# Sheet1.net
KiCad netlist of a schematic drawn in Altium Designer
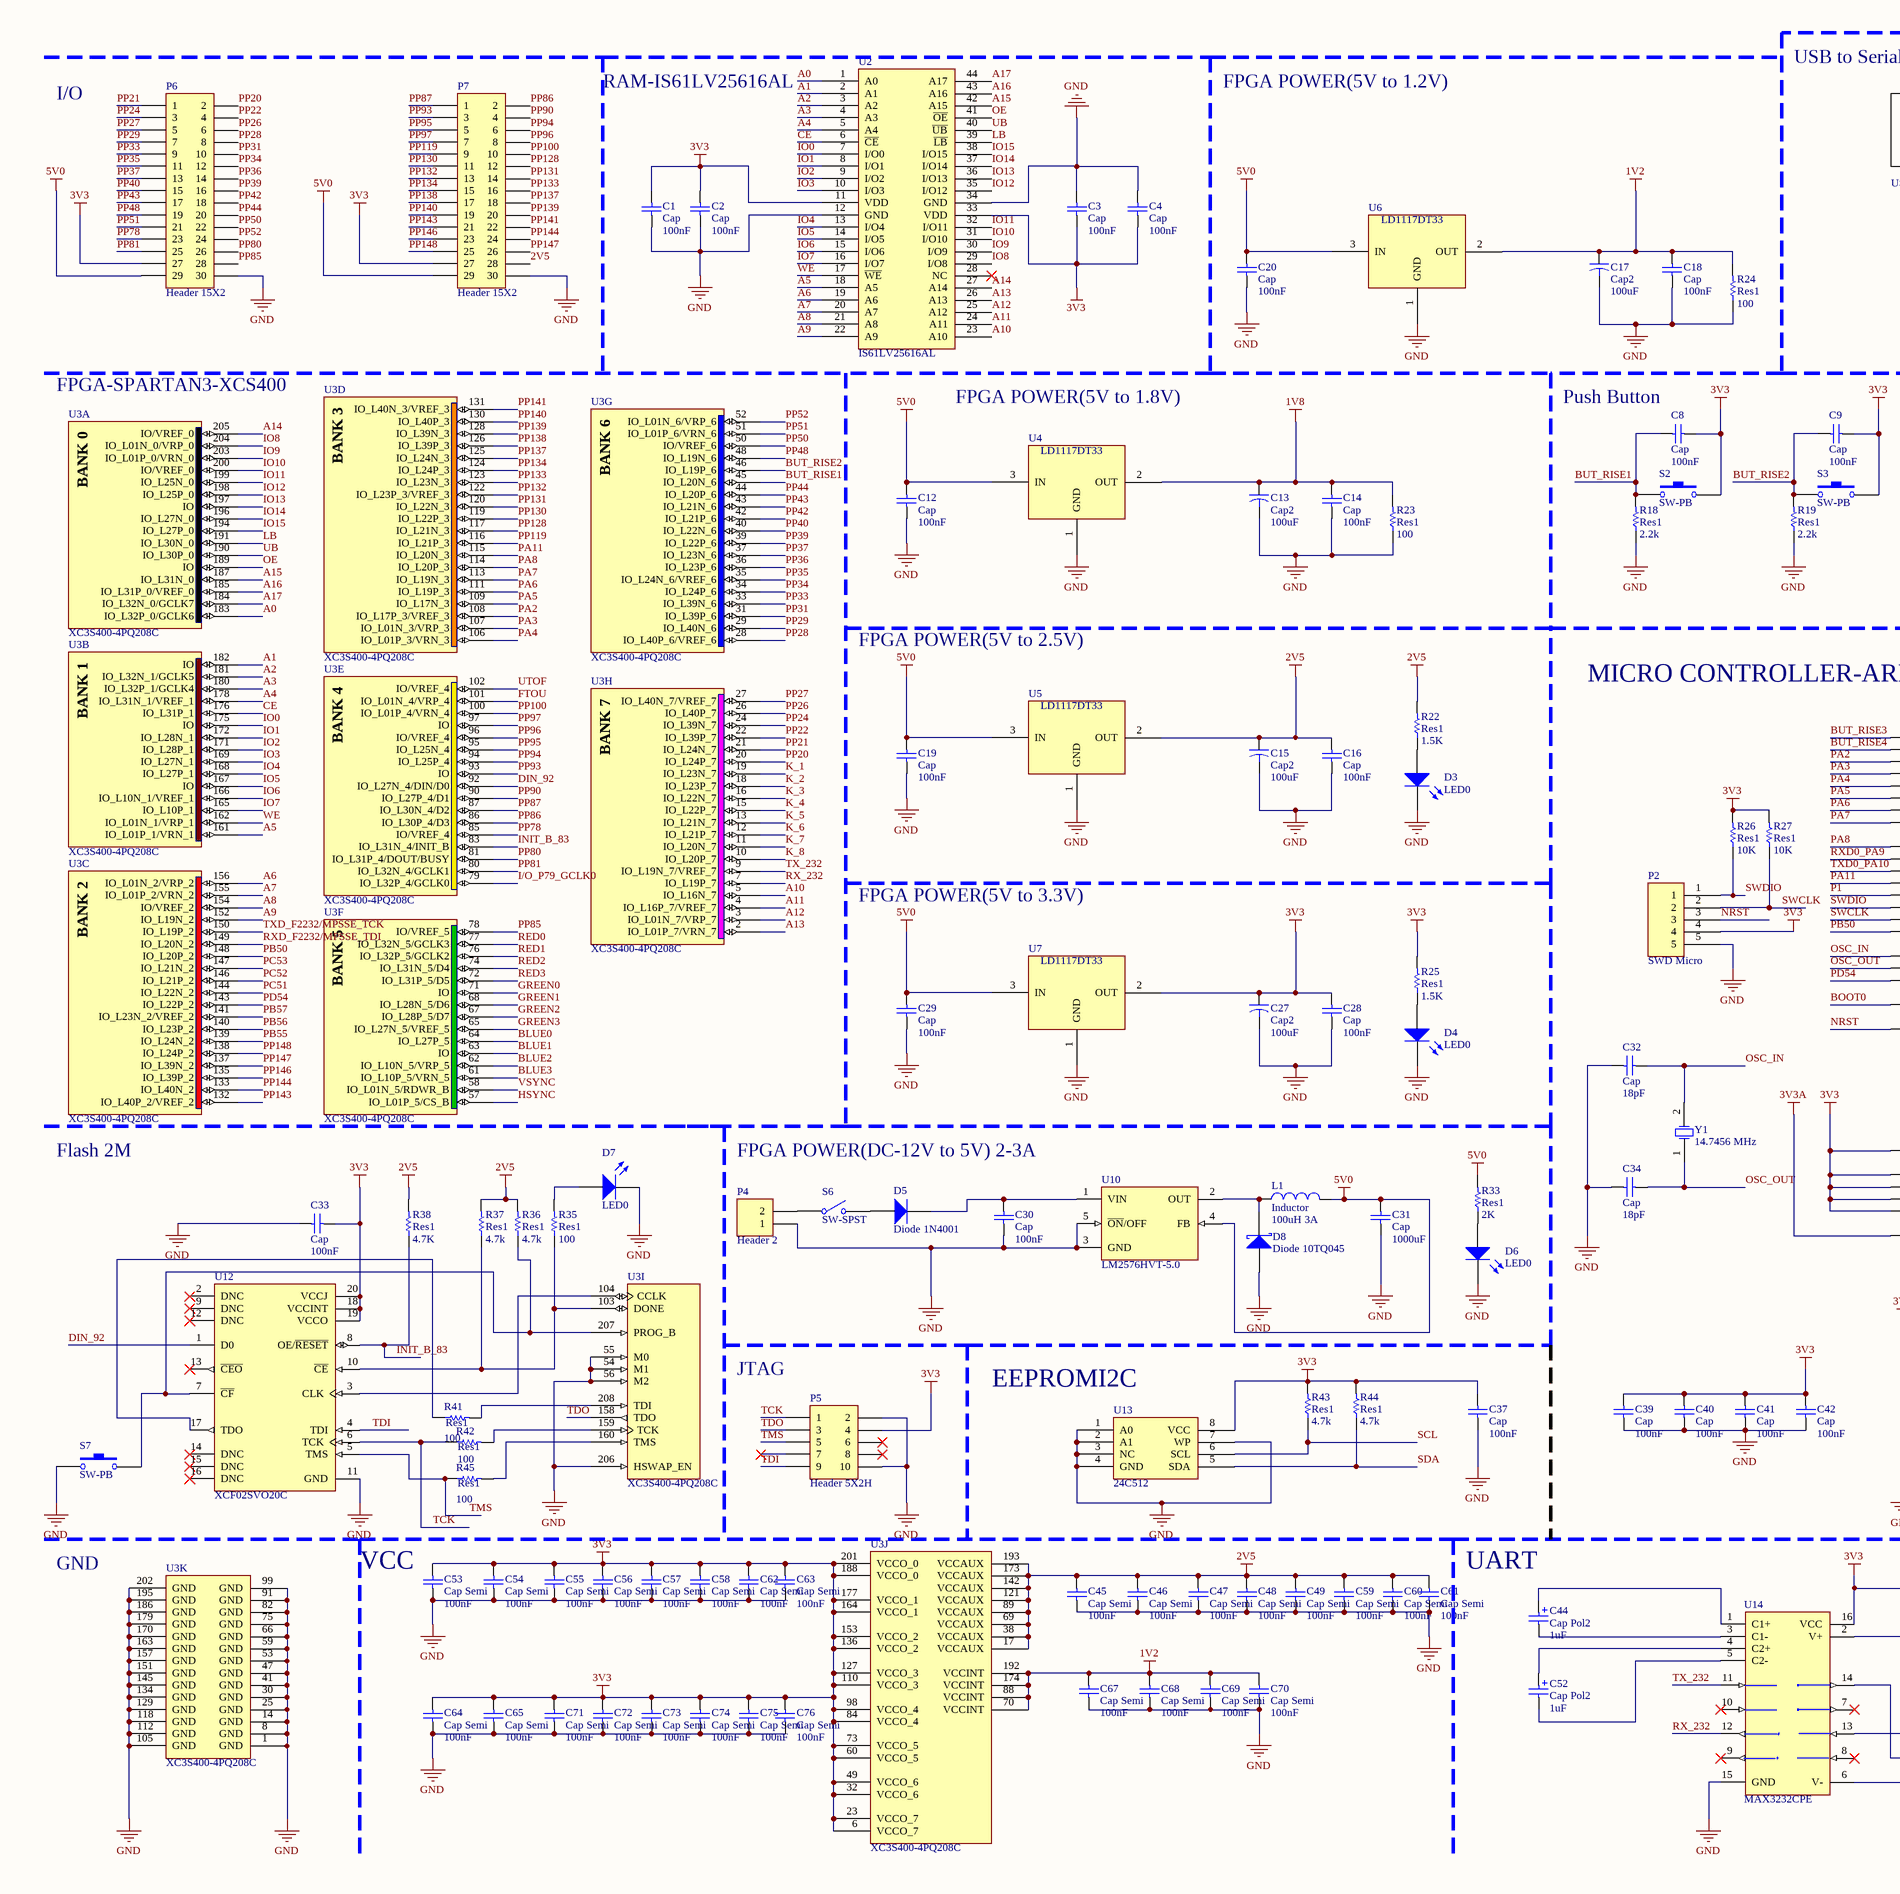
[diagram p0: Sheet1.SchDoc, left]
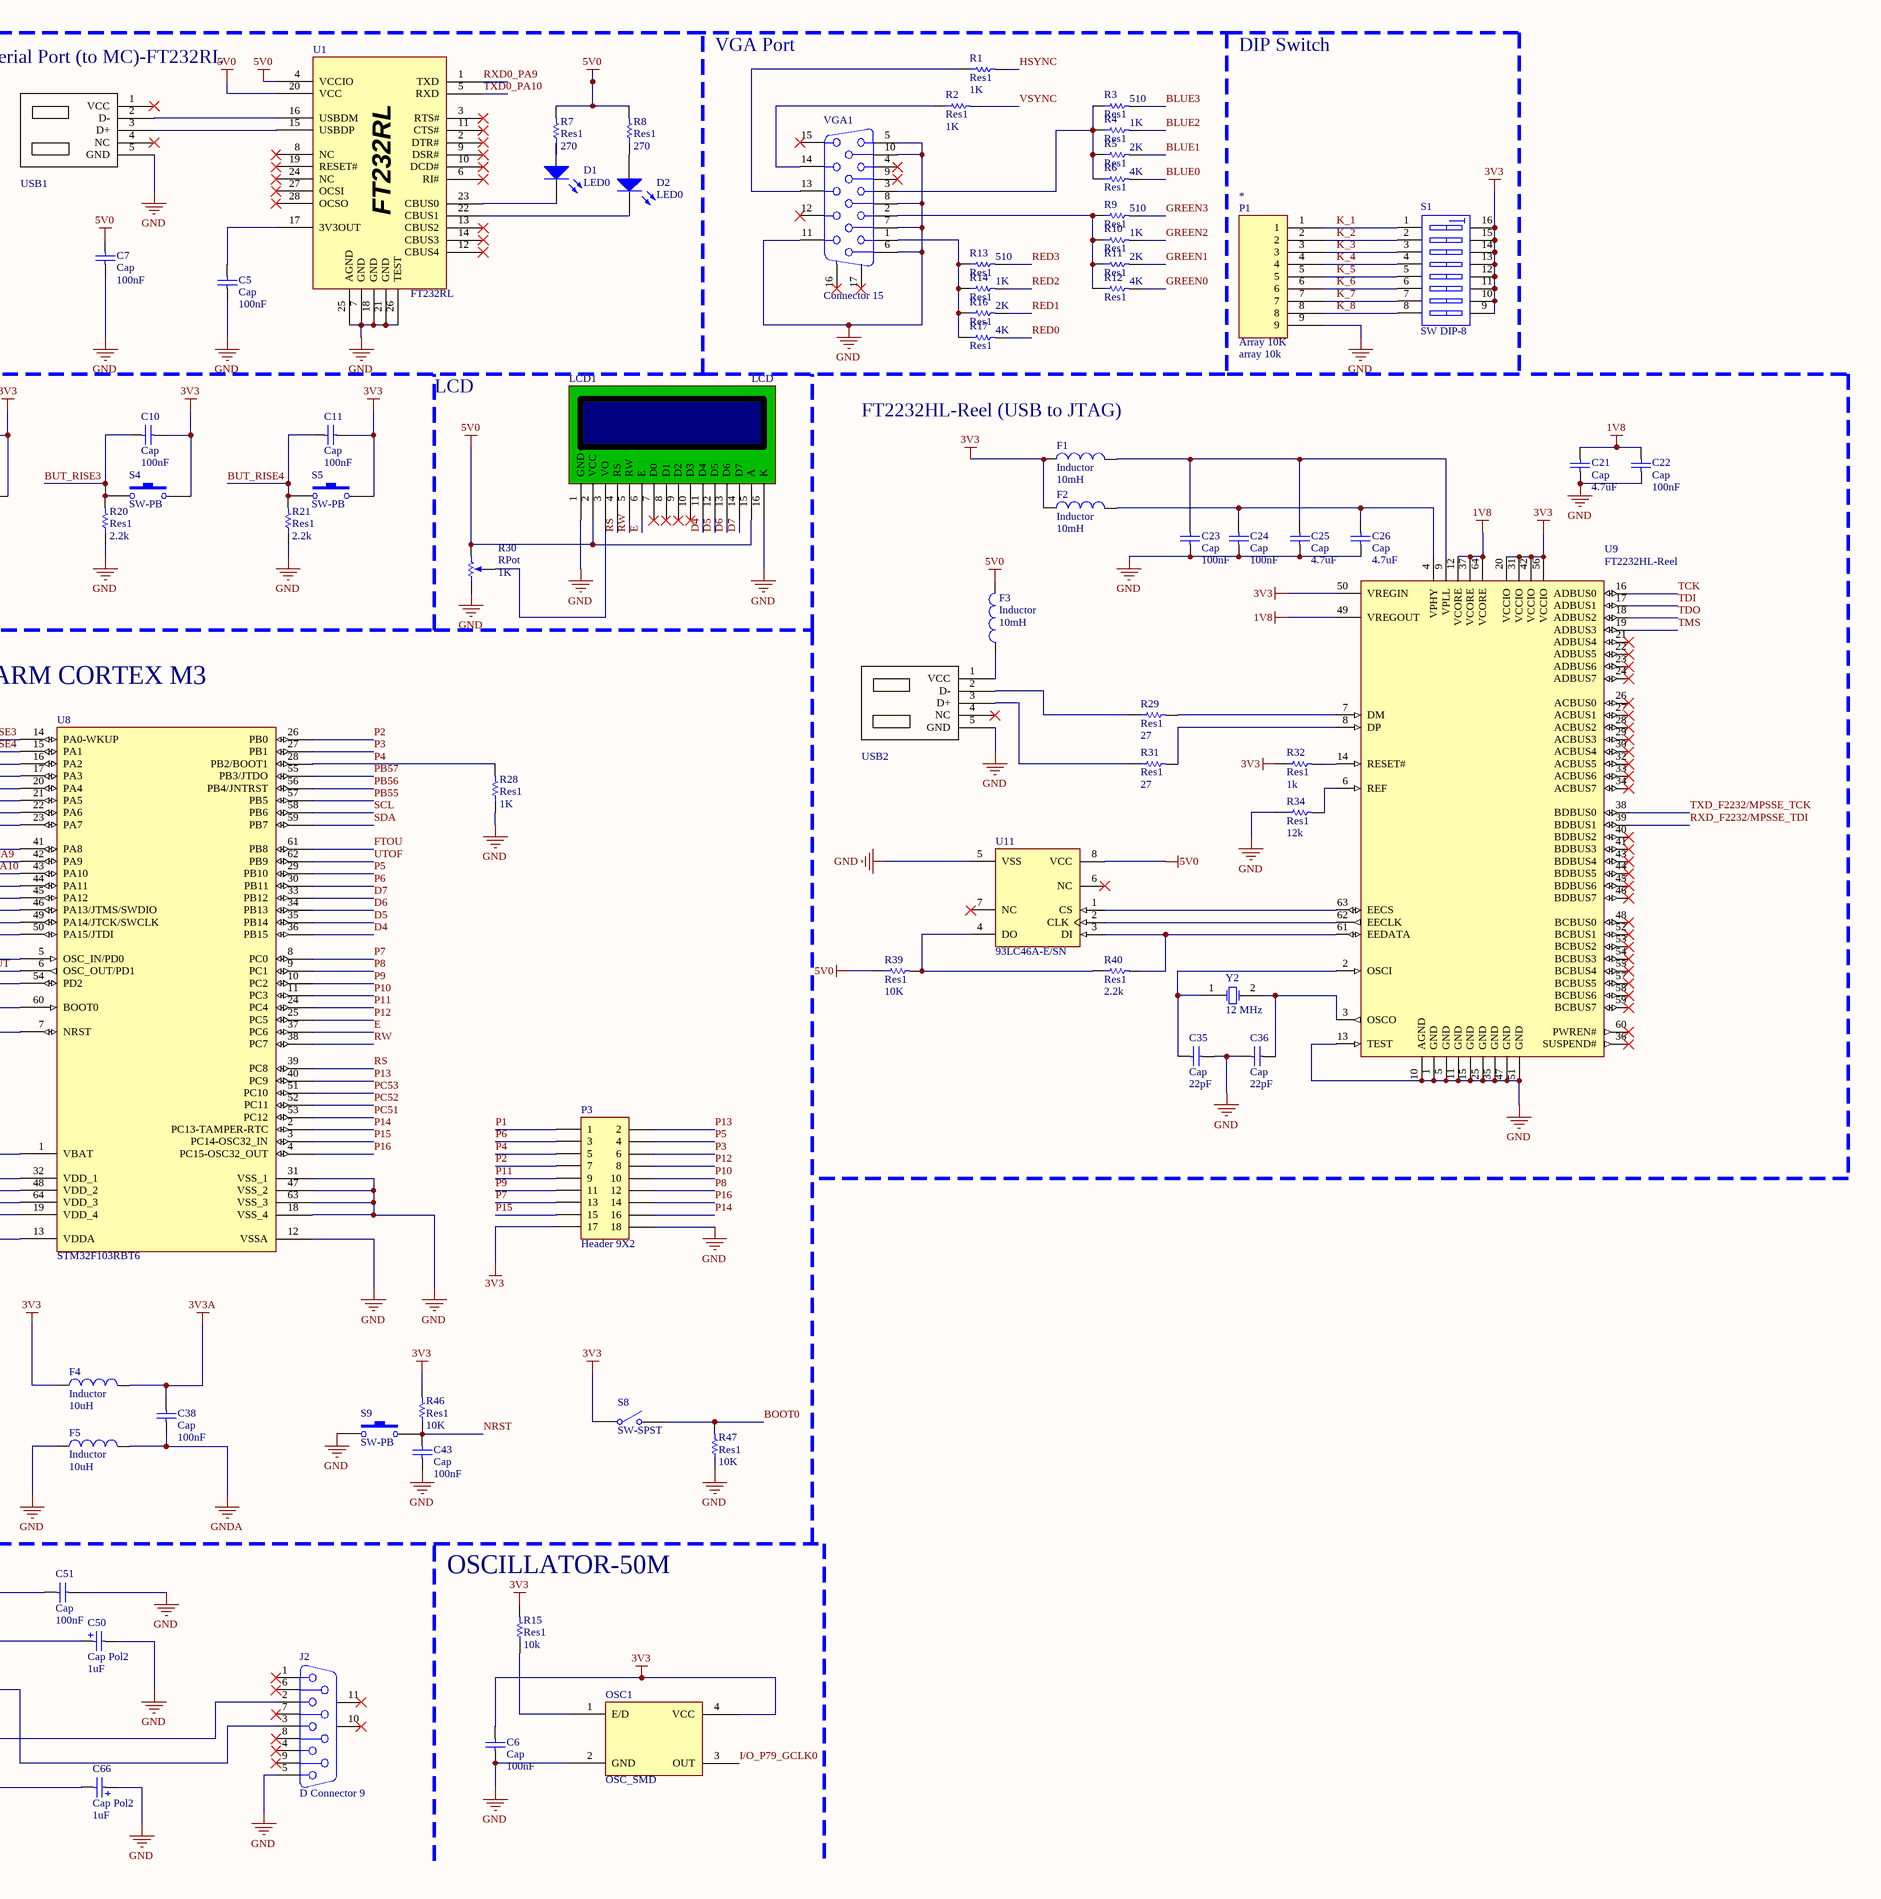
[diagram p1: Sheet1.SchDoc, right]

(export (version "E")
  (design (tool "Eeschema 10.0.6"))
  (components
    (comp (ref "*") (value "array 10k") (footprint "Aray 9") (libsource (lib "Array10k") (part "array 10k")))
    (comp (ref "C1")
      (value "Cap")
      (footprint "SMD_805")
      (description "Capacitor")
      (fields (field (name "ALTIUM_VALUE") "100nF") (field (name "PUBLISHER") "Altium Limited"))
      (libsource (lib "Miscellaneous Devices") (part "Cap"))
    )
    (comp (ref "C2")
      (value "Cap")
      (footprint "SMD_805")
      (description "Capacitor")
      (fields (field (name "ALTIUM_VALUE") "100nF") (field (name "PUBLISHER") "Altium Limited"))
      (libsource (lib "Miscellaneous Devices") (part "Cap"))
    )
    (comp (ref "C3")
      (value "Cap")
      (footprint "SMD_805")
      (description "Capacitor")
      (fields (field (name "ALTIUM_VALUE") "100nF") (field (name "PUBLISHER") "Altium Limited"))
      (libsource (lib "Miscellaneous Devices") (part "Cap"))
    )
    (comp (ref "C4")
      (value "Cap")
      (footprint "SMD_805")
      (description "Capacitor")
      (fields (field (name "ALTIUM_VALUE") "100nF") (field (name "PUBLISHER") "Altium Limited"))
      (libsource (lib "Miscellaneous Devices") (part "Cap"))
    )
    (comp (ref "C5")
      (value "Cap")
      (footprint "SMD_805")
      (description "Capacitor")
      (fields (field (name "ALTIUM_VALUE") "100nF") (field (name "PUBLISHER") "Altium Limited"))
      (libsource (lib "Miscellaneous Devices") (part "Cap"))
    )
    (comp (ref "C6")
      (value "Cap")
      (footprint "SMD_805")
      (description "Capacitor")
      (fields (field (name "ALTIUM_VALUE") "100nF") (field (name "PUBLISHER") "Altium Limited"))
      (libsource (lib "Miscellaneous Devices") (part "Cap"))
    )
    (comp (ref "C7")
      (value "Cap")
      (footprint "SMD_805")
      (description "Capacitor")
      (fields (field (name "ALTIUM_VALUE") "100nF") (field (name "PUBLISHER") "Altium Limited"))
      (libsource (lib "Miscellaneous Devices") (part "Cap"))
    )
    (comp (ref "C8")
      (value "Cap")
      (footprint "SMD_805")
      (description "Capacitor")
      (fields (field (name "ALTIUM_VALUE") "100nF") (field (name "PUBLISHER") "Altium Limited"))
      (libsource (lib "Miscellaneous Devices") (part "Cap"))
    )
    (comp (ref "C9")
      (value "Cap")
      (footprint "SMD_805")
      (description "Capacitor")
      (fields (field (name "ALTIUM_VALUE") "100nF") (field (name "PUBLISHER") "Altium Limited"))
      (libsource (lib "Miscellaneous Devices") (part "Cap"))
    )
    (comp (ref "C10")
      (value "Cap")
      (footprint "SMD_805")
      (description "Capacitor")
      (fields (field (name "ALTIUM_VALUE") "100nF") (field (name "PUBLISHER") "Altium Limited"))
      (libsource (lib "Miscellaneous Devices") (part "Cap"))
    )
    (comp (ref "C11")
      (value "Cap")
      (footprint "SMD_805")
      (description "Capacitor")
      (fields (field (name "ALTIUM_VALUE") "100nF") (field (name "PUBLISHER") "Altium Limited"))
      (libsource (lib "Miscellaneous Devices") (part "Cap"))
    )
    (comp (ref "C12")
      (value "Cap")
      (footprint "SMD_805")
      (description "Capacitor")
      (fields (field (name "ALTIUM_VALUE") "100nF") (field (name "PUBLISHER") "Altium Limited"))
      (libsource (lib "Miscellaneous Devices") (part "Cap"))
    )
    (comp (ref "C13")
      (value "Cap2")
      (footprint "C_B")
      (description "Capacitor")
      (fields (field (name "ALTIUM_VALUE") "100uF") (field (name "PUBLISHER") "Altium Limited"))
      (libsource (lib "Miscellaneous Devices") (part "Cap2"))
    )
    (comp (ref "C14")
      (value "Cap")
      (footprint "SMD_805")
      (description "Capacitor")
      (fields (field (name "ALTIUM_VALUE") "100nF") (field (name "PUBLISHER") "Altium Limited"))
      (libsource (lib "Miscellaneous Devices") (part "Cap"))
    )
    (comp (ref "C15")
      (value "Cap2")
      (footprint "C_B")
      (description "Capacitor")
      (fields (field (name "ALTIUM_VALUE") "100uF") (field (name "PUBLISHER") "Altium Limited"))
      (libsource (lib "Miscellaneous Devices") (part "Cap2"))
    )
    (comp (ref "C16")
      (value "Cap")
      (footprint "SMD_805")
      (description "Capacitor")
      (fields (field (name "ALTIUM_VALUE") "100nF") (field (name "PUBLISHER") "Altium Limited"))
      (libsource (lib "Miscellaneous Devices") (part "Cap"))
    )
    (comp (ref "C17")
      (value "Cap2")
      (footprint "C_B")
      (description "Capacitor")
      (fields (field (name "ALTIUM_VALUE") "100uF") (field (name "PUBLISHER") "Altium Limited"))
      (libsource (lib "Miscellaneous Devices") (part "Cap2"))
    )
    (comp (ref "C18")
      (value "Cap")
      (footprint "SMD_805")
      (description "Capacitor")
      (fields (field (name "ALTIUM_VALUE") "100nF") (field (name "PUBLISHER") "Altium Limited"))
      (libsource (lib "Miscellaneous Devices") (part "Cap"))
    )
    (comp (ref "C19")
      (value "Cap")
      (footprint "SMD_805")
      (description "Capacitor")
      (fields (field (name "ALTIUM_VALUE") "100nF") (field (name "PUBLISHER") "Altium Limited"))
      (libsource (lib "Miscellaneous Devices") (part "Cap"))
    )
    (comp (ref "C20")
      (value "Cap")
      (footprint "SMD_805")
      (description "Capacitor")
      (fields (field (name "ALTIUM_VALUE") "100nF") (field (name "PUBLISHER") "Altium Limited"))
      (libsource (lib "Miscellaneous Devices") (part "Cap"))
    )
    (comp (ref "C21")
      (value "Cap")
      (footprint "SMD_805")
      (description "Capacitor")
      (fields (field (name "ALTIUM_VALUE") "4.7uF") (field (name "PUBLISHER") "Altium Limited"))
      (libsource (lib "Miscellaneous Devices") (part "Cap"))
    )
    (comp (ref "C22")
      (value "Cap")
      (footprint "SMD_805")
      (description "Capacitor")
      (fields (field (name "ALTIUM_VALUE") "100nF") (field (name "PUBLISHER") "Altium Limited"))
      (libsource (lib "Miscellaneous Devices") (part "Cap"))
    )
    (comp (ref "C23")
      (value "Cap")
      (footprint "SMD_805")
      (description "Capacitor")
      (fields (field (name "ALTIUM_VALUE") "100nF") (field (name "PUBLISHER") "Altium Limited"))
      (libsource (lib "Miscellaneous Devices") (part "Cap"))
    )
    (comp (ref "C24")
      (value "Cap")
      (footprint "SMD_805")
      (description "Capacitor")
      (fields (field (name "ALTIUM_VALUE") "100nF") (field (name "PUBLISHER") "Altium Limited"))
      (libsource (lib "Miscellaneous Devices") (part "Cap"))
    )
    (comp (ref "C25")
      (value "Cap")
      (footprint "SMD_805")
      (description "Capacitor")
      (fields (field (name "ALTIUM_VALUE") "4.7uF") (field (name "PUBLISHER") "Altium Limited"))
      (libsource (lib "Miscellaneous Devices") (part "Cap"))
    )
    (comp (ref "C26")
      (value "Cap")
      (footprint "SMD_805")
      (description "Capacitor")
      (fields (field (name "ALTIUM_VALUE") "4.7uF") (field (name "PUBLISHER") "Altium Limited"))
      (libsource (lib "Miscellaneous Devices") (part "Cap"))
    )
    (comp (ref "C27")
      (value "Cap2")
      (footprint "C_B")
      (description "Capacitor")
      (fields (field (name "ALTIUM_VALUE") "100uF") (field (name "PUBLISHER") "Altium Limited"))
      (libsource (lib "Miscellaneous Devices") (part "Cap2"))
    )
    (comp (ref "C28")
      (value "Cap")
      (footprint "SMD_805")
      (description "Capacitor")
      (fields (field (name "ALTIUM_VALUE") "100nF") (field (name "PUBLISHER") "Altium Limited"))
      (libsource (lib "Miscellaneous Devices") (part "Cap"))
    )
    (comp (ref "C29")
      (value "Cap")
      (footprint "SMD_805")
      (description "Capacitor")
      (fields (field (name "ALTIUM_VALUE") "100nF") (field (name "PUBLISHER") "Altium Limited"))
      (libsource (lib "Miscellaneous Devices") (part "Cap"))
    )
    (comp (ref "C30")
      (value "Cap")
      (footprint "C_CYL_SMD2")
      (description "Capacitor")
      (fields (field (name "ALTIUM_VALUE") "100nF") (field (name "PUBLISHER") "Altium Limited"))
      (libsource (lib "Miscellaneous Devices") (part "Cap"))
    )
    (comp (ref "C31")
      (value "Cap")
      (footprint "C_CYL_SMD")
      (description "Capacitor")
      (fields (field (name "ALTIUM_VALUE") "1000uF") (field (name "PUBLISHER") "Altium Limited"))
      (libsource (lib "Miscellaneous Devices") (part "Cap"))
    )
    (comp (ref "C32")
      (value "Cap")
      (footprint "SMD_805")
      (description "Capacitor")
      (fields (field (name "ALTIUM_VALUE") "18pF") (field (name "PUBLISHER") "Altium Limited"))
      (libsource (lib "Miscellaneous Devices") (part "Cap"))
    )
    (comp (ref "C33")
      (value "Cap")
      (footprint "SMD_805")
      (description "Capacitor")
      (fields (field (name "ALTIUM_VALUE") "100nF") (field (name "PUBLISHER") "Altium Limited"))
      (libsource (lib "Miscellaneous Devices") (part "Cap"))
    )
    (comp (ref "C34")
      (value "Cap")
      (footprint "SMD_805")
      (description "Capacitor")
      (fields (field (name "ALTIUM_VALUE") "18pF") (field (name "PUBLISHER") "Altium Limited"))
      (libsource (lib "Miscellaneous Devices") (part "Cap"))
    )
    (comp (ref "C35")
      (value "Cap")
      (footprint "SMD_805")
      (description "Capacitor")
      (fields (field (name "ALTIUM_VALUE") "22pF") (field (name "PUBLISHER") "Altium Limited"))
      (libsource (lib "Miscellaneous Devices") (part "Cap"))
    )
    (comp (ref "C36")
      (value "Cap")
      (footprint "SMD_805")
      (description "Capacitor")
      (fields (field (name "ALTIUM_VALUE") "22pF") (field (name "PUBLISHER") "Altium Limited"))
      (libsource (lib "Miscellaneous Devices") (part "Cap"))
    )
    (comp (ref "C37")
      (value "Cap")
      (footprint "SMD_805")
      (description "Capacitor")
      (fields (field (name "ALTIUM_VALUE") "100nF") (field (name "PUBLISHER") "Altium Limited"))
      (libsource (lib "Miscellaneous Devices") (part "Cap"))
    )
    (comp (ref "C38")
      (value "Cap")
      (footprint "SMD_805")
      (description "Capacitor")
      (fields (field (name "ALTIUM_VALUE") "100nF") (field (name "PUBLISHER") "Altium Limited"))
      (libsource (lib "Miscellaneous Devices") (part "Cap"))
    )
    (comp (ref "C39")
      (value "Cap")
      (footprint "SMD_805")
      (description "Capacitor")
      (fields (field (name "ALTIUM_VALUE") "100nF") (field (name "PUBLISHER") "Altium Limited"))
      (libsource (lib "Miscellaneous Devices") (part "Cap"))
    )
    (comp (ref "C40")
      (value "Cap")
      (footprint "SMD_805")
      (description "Capacitor")
      (fields (field (name "ALTIUM_VALUE") "100nF") (field (name "PUBLISHER") "Altium Limited"))
      (libsource (lib "Miscellaneous Devices") (part "Cap"))
    )
    (comp (ref "C41")
      (value "Cap")
      (footprint "SMD_805")
      (description "Capacitor")
      (fields (field (name "ALTIUM_VALUE") "100nF") (field (name "PUBLISHER") "Altium Limited"))
      (libsource (lib "Miscellaneous Devices") (part "Cap"))
    )
    (comp (ref "C42")
      (value "Cap")
      (footprint "SMD_805")
      (description "Capacitor")
      (fields (field (name "ALTIUM_VALUE") "100nF") (field (name "PUBLISHER") "Altium Limited"))
      (libsource (lib "Miscellaneous Devices") (part "Cap"))
    )
    (comp (ref "C43")
      (value "Cap")
      (footprint "SMD_805")
      (description "Capacitor")
      (fields (field (name "ALTIUM_VALUE") "100nF") (field (name "PUBLISHER") "Altium Limited"))
      (libsource (lib "Miscellaneous Devices") (part "Cap"))
    )
    (comp (ref "C44")
      (value "Cap Pol2")
      (footprint "C_B")
      (description "Polarized Capacitor (Axial)")
      (fields (field (name "ALTIUM_VALUE") "1uF") (field (name "PUBLISHER") "Altium Limited"))
      (libsource (lib "Miscellaneous Devices") (part "Cap Pol2"))
    )
    (comp (ref "C45")
      (value "Cap Semi")
      (footprint "SMD_805")
      (description "Capacitor (Semiconductor SIM Model)")
      (fields (field (name "ALTIUM_VALUE") "100nF") (field (name "PUBLISHER") "Altium Limited"))
      (libsource (lib "Miscellaneous Devices") (part "Cap Semi"))
    )
    (comp (ref "C46")
      (value "Cap Semi")
      (footprint "SMD_805")
      (description "Capacitor (Semiconductor SIM Model)")
      (fields (field (name "ALTIUM_VALUE") "100nF") (field (name "PUBLISHER") "Altium Limited"))
      (libsource (lib "Miscellaneous Devices") (part "Cap Semi"))
    )
    (comp (ref "C47")
      (value "Cap Semi")
      (footprint "SMD_805")
      (description "Capacitor (Semiconductor SIM Model)")
      (fields (field (name "ALTIUM_VALUE") "100nF") (field (name "PUBLISHER") "Altium Limited"))
      (libsource (lib "Miscellaneous Devices") (part "Cap Semi"))
    )
    (comp (ref "C48")
      (value "Cap Semi")
      (footprint "SMD_805")
      (description "Capacitor (Semiconductor SIM Model)")
      (fields (field (name "ALTIUM_VALUE") "100nF") (field (name "PUBLISHER") "Altium Limited"))
      (libsource (lib "Miscellaneous Devices") (part "Cap Semi"))
    )
    (comp (ref "C49")
      (value "Cap Semi")
      (footprint "SMD_805")
      (description "Capacitor (Semiconductor SIM Model)")
      (fields (field (name "ALTIUM_VALUE") "100nF") (field (name "PUBLISHER") "Altium Limited"))
      (libsource (lib "Miscellaneous Devices") (part "Cap Semi"))
    )
    (comp (ref "C50")
      (value "Cap Pol2")
      (footprint "C_B")
      (description "Polarized Capacitor (Axial)")
      (fields (field (name "ALTIUM_VALUE") "1uF") (field (name "PUBLISHER") "Altium Limited"))
      (libsource (lib "Miscellaneous Devices") (part "Cap Pol2"))
    )
    (comp (ref "C51")
      (value "Cap")
      (footprint "SMD_805")
      (description "Capacitor")
      (fields (field (name "ALTIUM_VALUE") "100nF") (field (name "PUBLISHER") "Altium Limited"))
      (libsource (lib "Miscellaneous Devices") (part "Cap"))
    )
    (comp (ref "C52")
      (value "Cap Pol2")
      (footprint "C_B")
      (description "Polarized Capacitor (Axial)")
      (fields (field (name "ALTIUM_VALUE") "1uF") (field (name "PUBLISHER") "Altium Limited"))
      (libsource (lib "Miscellaneous Devices") (part "Cap Pol2"))
    )
    (comp (ref "C53")
      (value "Cap Semi")
      (footprint "SMD_805")
      (description "Capacitor (Semiconductor SIM Model)")
      (fields (field (name "ALTIUM_VALUE") "100nF") (field (name "PUBLISHER") "Altium Limited"))
      (libsource (lib "Miscellaneous Devices") (part "Cap Semi"))
    )
    (comp (ref "C54")
      (value "Cap Semi")
      (footprint "SMD_805")
      (description "Capacitor (Semiconductor SIM Model)")
      (fields (field (name "ALTIUM_VALUE") "100nF") (field (name "PUBLISHER") "Altium Limited"))
      (libsource (lib "Miscellaneous Devices") (part "Cap Semi"))
    )
    (comp (ref "C55")
      (value "Cap Semi")
      (footprint "SMD_805")
      (description "Capacitor (Semiconductor SIM Model)")
      (fields (field (name "ALTIUM_VALUE") "100nF") (field (name "PUBLISHER") "Altium Limited"))
      (libsource (lib "Miscellaneous Devices") (part "Cap Semi"))
    )
    (comp (ref "C56")
      (value "Cap Semi")
      (footprint "SMD_805")
      (description "Capacitor (Semiconductor SIM Model)")
      (fields (field (name "ALTIUM_VALUE") "100nF") (field (name "PUBLISHER") "Altium Limited"))
      (libsource (lib "Miscellaneous Devices") (part "Cap Semi"))
    )
    (comp (ref "C57")
      (value "Cap Semi")
      (footprint "SMD_805")
      (description "Capacitor (Semiconductor SIM Model)")
      (fields (field (name "ALTIUM_VALUE") "100nF") (field (name "PUBLISHER") "Altium Limited"))
      (libsource (lib "Miscellaneous Devices") (part "Cap Semi"))
    )
    (comp (ref "C58")
      (value "Cap Semi")
      (footprint "SMD_805")
      (description "Capacitor (Semiconductor SIM Model)")
      (fields (field (name "ALTIUM_VALUE") "100nF") (field (name "PUBLISHER") "Altium Limited"))
      (libsource (lib "Miscellaneous Devices") (part "Cap Semi"))
    )
    (comp (ref "C59")
      (value "Cap Semi")
      (footprint "SMD_805")
      (description "Capacitor (Semiconductor SIM Model)")
      (fields (field (name "ALTIUM_VALUE") "100nF") (field (name "PUBLISHER") "Altium Limited"))
      (libsource (lib "Miscellaneous Devices") (part "Cap Semi"))
    )
    (comp (ref "C60")
      (value "Cap Semi")
      (footprint "SMD_805")
      (description "Capacitor (Semiconductor SIM Model)")
      (fields (field (name "ALTIUM_VALUE") "100nF") (field (name "PUBLISHER") "Altium Limited"))
      (libsource (lib "Miscellaneous Devices") (part "Cap Semi"))
    )
    (comp (ref "C61")
      (value "Cap Semi")
      (footprint "SMD_805")
      (description "Capacitor (Semiconductor SIM Model)")
      (fields (field (name "ALTIUM_VALUE") "100nF") (field (name "PUBLISHER") "Altium Limited"))
      (libsource (lib "Miscellaneous Devices") (part "Cap Semi"))
    )
    (comp (ref "C62")
      (value "Cap Semi")
      (footprint "SMD_805")
      (description "Capacitor (Semiconductor SIM Model)")
      (fields (field (name "ALTIUM_VALUE") "100nF") (field (name "PUBLISHER") "Altium Limited"))
      (libsource (lib "Miscellaneous Devices") (part "Cap Semi"))
    )
    (comp (ref "C63")
      (value "Cap Semi")
      (footprint "SMD_805")
      (description "Capacitor (Semiconductor SIM Model)")
      (fields (field (name "ALTIUM_VALUE") "100nF") (field (name "PUBLISHER") "Altium Limited"))
      (libsource (lib "Miscellaneous Devices") (part "Cap Semi"))
    )
    (comp (ref "C64")
      (value "Cap Semi")
      (footprint "SMD_805")
      (description "Capacitor (Semiconductor SIM Model)")
      (fields (field (name "ALTIUM_VALUE") "100nF") (field (name "PUBLISHER") "Altium Limited"))
      (libsource (lib "Miscellaneous Devices") (part "Cap Semi"))
    )
    (comp (ref "C65")
      (value "Cap Semi")
      (footprint "SMD_805")
      (description "Capacitor (Semiconductor SIM Model)")
      (fields (field (name "ALTIUM_VALUE") "100nF") (field (name "PUBLISHER") "Altium Limited"))
      (libsource (lib "Miscellaneous Devices") (part "Cap Semi"))
    )
    (comp (ref "C66")
      (value "Cap Pol2")
      (footprint "C_B")
      (description "Polarized Capacitor (Axial)")
      (fields (field (name "ALTIUM_VALUE") "1uF") (field (name "PUBLISHER") "Altium Limited"))
      (libsource (lib "Miscellaneous Devices") (part "Cap Pol2"))
    )
    (comp (ref "C67")
      (value "Cap Semi")
      (footprint "SMD_805")
      (description "Capacitor (Semiconductor SIM Model)")
      (fields (field (name "ALTIUM_VALUE") "100nF") (field (name "PUBLISHER") "Altium Limited"))
      (libsource (lib "Miscellaneous Devices") (part "Cap Semi"))
    )
    (comp (ref "C68")
      (value "Cap Semi")
      (footprint "SMD_805")
      (description "Capacitor (Semiconductor SIM Model)")
      (fields (field (name "ALTIUM_VALUE") "100nF") (field (name "PUBLISHER") "Altium Limited"))
      (libsource (lib "Miscellaneous Devices") (part "Cap Semi"))
    )
    (comp (ref "C69")
      (value "Cap Semi")
      (footprint "SMD_805")
      (description "Capacitor (Semiconductor SIM Model)")
      (fields (field (name "ALTIUM_VALUE") "100nF") (field (name "PUBLISHER") "Altium Limited"))
      (libsource (lib "Miscellaneous Devices") (part "Cap Semi"))
    )
    (comp (ref "C70")
      (value "Cap Semi")
      (footprint "SMD_805")
      (description "Capacitor (Semiconductor SIM Model)")
      (fields (field (name "ALTIUM_VALUE") "100nF") (field (name "PUBLISHER") "Altium Limited"))
      (libsource (lib "Miscellaneous Devices") (part "Cap Semi"))
    )
    (comp (ref "C71")
      (value "Cap Semi")
      (footprint "SMD_805")
      (description "Capacitor (Semiconductor SIM Model)")
      (fields (field (name "ALTIUM_VALUE") "100nF") (field (name "PUBLISHER") "Altium Limited"))
      (libsource (lib "Miscellaneous Devices") (part "Cap Semi"))
    )
    (comp (ref "C72")
      (value "Cap Semi")
      (footprint "SMD_805")
      (description "Capacitor (Semiconductor SIM Model)")
      (fields (field (name "ALTIUM_VALUE") "100nF") (field (name "PUBLISHER") "Altium Limited"))
      (libsource (lib "Miscellaneous Devices") (part "Cap Semi"))
    )
    (comp (ref "C73")
      (value "Cap Semi")
      (footprint "SMD_805")
      (description "Capacitor (Semiconductor SIM Model)")
      (fields (field (name "ALTIUM_VALUE") "100nF") (field (name "PUBLISHER") "Altium Limited"))
      (libsource (lib "Miscellaneous Devices") (part "Cap Semi"))
    )
    (comp (ref "C74")
      (value "Cap Semi")
      (footprint "SMD_805")
      (description "Capacitor (Semiconductor SIM Model)")
      (fields (field (name "ALTIUM_VALUE") "100nF") (field (name "PUBLISHER") "Altium Limited"))
      (libsource (lib "Miscellaneous Devices") (part "Cap Semi"))
    )
    (comp (ref "C75")
      (value "Cap Semi")
      (footprint "SMD_805")
      (description "Capacitor (Semiconductor SIM Model)")
      (fields (field (name "ALTIUM_VALUE") "100nF") (field (name "PUBLISHER") "Altium Limited"))
      (libsource (lib "Miscellaneous Devices") (part "Cap Semi"))
    )
    (comp (ref "C76")
      (value "Cap Semi")
      (footprint "SMD_805")
      (description "Capacitor (Semiconductor SIM Model)")
      (fields (field (name "ALTIUM_VALUE") "100nF") (field (name "PUBLISHER") "Altium Limited"))
      (libsource (lib "Miscellaneous Devices") (part "Cap Semi"))
    )
    (comp (ref "D1")
      (value "LED0")
      (footprint "SMD_805")
      (description "Typical INFRARED GaAs LED")
      (fields (field (name "PUBLISHER") "Altium Limited"))
      (libsource (lib "Miscellaneous Devices") (part "LED0"))
    )
    (comp (ref "D2")
      (value "LED0")
      (footprint "SMD_805")
      (description "Typical INFRARED GaAs LED")
      (fields (field (name "PUBLISHER") "Altium Limited"))
      (libsource (lib "Miscellaneous Devices") (part "LED0"))
    )
    (comp (ref "D3")
      (value "LED0")
      (footprint "SMD_805")
      (description "Typical INFRARED GaAs LED")
      (fields (field (name "PUBLISHER") "Altium Limited"))
      (libsource (lib "Miscellaneous Devices") (part "LED0"))
    )
    (comp (ref "D4")
      (value "LED0")
      (footprint "SMD_805")
      (description "Typical INFRARED GaAs LED")
      (fields (field (name "PUBLISHER") "Altium Limited"))
      (libsource (lib "Miscellaneous Devices") (part "LED0"))
    )
    (comp (ref "D5")
      (value "Diode 1N4001")
      (footprint "TVS")
      (description "1 Amp General Purpose Rectifier")
      (fields (field (name "PUBLISHER") "Altium Limited"))
      (libsource (lib "Miscellaneous Devices") (part "Diode 1N4001"))
    )
    (comp (ref "D6")
      (value "LED0")
      (footprint "SMD_805")
      (description "Typical INFRARED GaAs LED")
      (fields (field (name "PUBLISHER") "Altium Limited"))
      (libsource (lib "Miscellaneous Devices") (part "LED0"))
    )
    (comp (ref "D7")
      (value "LED0")
      (footprint "SMD_805")
      (description "Typical INFRARED GaAs LED")
      (fields (field (name "PUBLISHER") "Altium Limited"))
      (libsource (lib "Miscellaneous Devices") (part "LED0"))
    )
    (comp (ref "D8")
      (value "Diode 10TQ045")
      (footprint "1N5822")
      (description "Schottky Rectifier")
      (fields (field (name "PUBLISHER") "Altium Limited"))
      (libsource (lib "Miscellaneous Devices") (part "Diode 10TQ045"))
    )
    (comp (ref "F1")
      (value "Inductor")
      (footprint "SMD_805")
      (fields (field (name "ALTIUM_VALUE") "10mH") (field (name "PUBLISHER") "Altium Limited"))
      (libsource (lib "Miscellaneous Devices") (part "Inductor"))
    )
    (comp (ref "F2")
      (value "Inductor")
      (footprint "SMD_805")
      (fields (field (name "ALTIUM_VALUE") "10mH") (field (name "PUBLISHER") "Altium Limited"))
      (libsource (lib "Miscellaneous Devices") (part "Inductor"))
    )
    (comp (ref "F3")
      (value "Inductor")
      (footprint "SMD_805")
      (fields (field (name "ALTIUM_VALUE") "10mH") (field (name "PUBLISHER") "Altium Limited"))
      (libsource (lib "Miscellaneous Devices") (part "Inductor"))
    )
    (comp (ref "F4")
      (value "Inductor")
      (footprint "SMD_805")
      (fields (field (name "ALTIUM_VALUE") "10uH") (field (name "PUBLISHER") "Altium Limited"))
      (libsource (lib "Miscellaneous Devices") (part "Inductor"))
    )
    (comp (ref "F5")
      (value "Inductor")
      (footprint "SMD_805")
      (fields (field (name "ALTIUM_VALUE") "10uH") (field (name "PUBLISHER") "Altium Limited"))
      (libsource (lib "Miscellaneous Devices") (part "Inductor"))
    )
    (comp (ref "J2")
      (value "D Connector 9")
      (footprint "COM_3d")
      (description "Receptacle Assembly, 9 Position, Right Angle")
      (fields (field (name "PUBLISHER") "Altium Limited"))
      (libsource (lib "Miscellaneous Connectors") (part "D Connector 9"))
    )
    (comp (ref "L1")
      (value "Inductor")
      (footprint "INDUC_SMD")
      (fields (field (name "ALTIUM_VALUE") "100uH 3A") (field (name "PUBLISHER") "Altium Limited"))
      (libsource (lib "Miscellaneous Devices") (part "Inductor"))
    )
    (comp (ref "LCD1") (value "LCD") (footprint "LCD2x16_3d") (libsource (lib "LCD") (part "LCD")))
    (comp (ref "OSC1")
      (value "OSC_SMD")
      (footprint "OSC_SMD")
      (fields (field (name "DESIGNER:") "Mohammad Ansari"))
      (libsource (lib "OSC_SMD") (part "Component_1"))
    )
    (comp (ref "P2") (value "P") (footprint "H5") (libsource (lib "swd_micro") (part "Component_1")))
    (comp (ref "P3")
      (value "Header 9X2")
      (footprint "HDR2X9")
      (description "Header, 9-Pin, Dual row")
      (fields (field (name "PUBLISHER") "Altium Limited"))
      (libsource (lib "Miscellaneous Connectors") (part "Header 9X2"))
    )
    (comp (ref "P4")
      (value "Header 2")
      (footprint "ADAP_JACK")
      (description "Header, 2-Pin")
      (fields (field (name "PUBLISHER") "Altium Limited"))
      (libsource (lib "Miscellaneous Connectors") (part "Header 2"))
    )
    (comp (ref "P5")
      (value "Header 5X2H")
      (footprint "BOX2x5_3D")
      (description "Header, 5-Pin, Dual row, Right Angle")
      (fields (field (name "PUBLISHER") "Altium Limited"))
      (libsource (lib "Miscellaneous Connectors") (part "Header 5X2H"))
    )
    (comp (ref "P6")
      (value "Header 15X2")
      (footprint "HDR2X15")
      (description "Header, 15-Pin, Dual row")
      (fields (field (name "PUBLISHER") "Altium Limited"))
      (libsource (lib "Miscellaneous Connectors") (part "Header 15X2"))
    )
    (comp (ref "P7")
      (value "Header 15X2")
      (footprint "HDR2X15")
      (description "Header, 15-Pin, Dual row")
      (fields (field (name "PUBLISHER") "Altium Limited"))
      (libsource (lib "Miscellaneous Connectors") (part "Header 15X2"))
    )
    (comp (ref "R1")
      (value "Res1")
      (footprint "SMD_805")
      (description "Resistor")
      (fields (field (name "ALTIUM_VALUE") "1K") (field (name "PUBLISHER") "Altium Limited"))
      (libsource (lib "Miscellaneous Devices") (part "Res1"))
    )
    (comp (ref "R2")
      (value "Res1")
      (footprint "SMD_805")
      (description "Resistor")
      (fields (field (name "ALTIUM_VALUE") "1K") (field (name "PUBLISHER") "Altium Limited"))
      (libsource (lib "Miscellaneous Devices") (part "Res1"))
    )
    (comp (ref "R3")
      (value "Res1")
      (footprint "SMD_805")
      (description "Resistor")
      (fields (field (name "ALTIUM_VALUE") "510") (field (name "PUBLISHER") "Altium Limited"))
      (libsource (lib "Miscellaneous Devices") (part "Res1"))
    )
    (comp (ref "R4")
      (value "Res1")
      (footprint "SMD_805")
      (description "Resistor")
      (fields (field (name "ALTIUM_VALUE") "1K") (field (name "PUBLISHER") "Altium Limited"))
      (libsource (lib "Miscellaneous Devices") (part "Res1"))
    )
    (comp (ref "R5")
      (value "Res1")
      (footprint "SMD_805")
      (description "Resistor")
      (fields (field (name "ALTIUM_VALUE") "2K") (field (name "PUBLISHER") "Altium Limited"))
      (libsource (lib "Miscellaneous Devices") (part "Res1"))
    )
    (comp (ref "R6")
      (value "Res1")
      (footprint "SMD_805")
      (description "Resistor")
      (fields (field (name "ALTIUM_VALUE") "4K") (field (name "PUBLISHER") "Altium Limited"))
      (libsource (lib "Miscellaneous Devices") (part "Res1"))
    )
    (comp (ref "R7")
      (value "Res1")
      (footprint "SMD_805")
      (description "Resistor")
      (fields (field (name "ALTIUM_VALUE") "270") (field (name "PUBLISHER") "Altium Limited"))
      (libsource (lib "Miscellaneous Devices") (part "Res1"))
    )
    (comp (ref "R8")
      (value "Res1")
      (footprint "SMD_805")
      (description "Resistor")
      (fields (field (name "ALTIUM_VALUE") "270") (field (name "PUBLISHER") "Altium Limited"))
      (libsource (lib "Miscellaneous Devices") (part "Res1"))
    )
    (comp (ref "R9")
      (value "Res1")
      (footprint "SMD_805")
      (description "Resistor")
      (fields (field (name "ALTIUM_VALUE") "510") (field (name "PUBLISHER") "Altium Limited"))
      (libsource (lib "Miscellaneous Devices") (part "Res1"))
    )
    (comp (ref "R10")
      (value "Res1")
      (footprint "SMD_805")
      (description "Resistor")
      (fields (field (name "ALTIUM_VALUE") "1K") (field (name "PUBLISHER") "Altium Limited"))
      (libsource (lib "Miscellaneous Devices") (part "Res1"))
    )
    (comp (ref "R11")
      (value "Res1")
      (footprint "SMD_805")
      (description "Resistor")
      (fields (field (name "ALTIUM_VALUE") "2K") (field (name "PUBLISHER") "Altium Limited"))
      (libsource (lib "Miscellaneous Devices") (part "Res1"))
    )
    (comp (ref "R12")
      (value "Res1")
      (footprint "SMD_805")
      (description "Resistor")
      (fields (field (name "ALTIUM_VALUE") "4K") (field (name "PUBLISHER") "Altium Limited"))
      (libsource (lib "Miscellaneous Devices") (part "Res1"))
    )
    (comp (ref "R13")
      (value "Res1")
      (footprint "SMD_805")
      (description "Resistor")
      (fields (field (name "ALTIUM_VALUE") "510") (field (name "PUBLISHER") "Altium Limited"))
      (libsource (lib "Miscellaneous Devices") (part "Res1"))
    )
    (comp (ref "R14")
      (value "Res1")
      (footprint "SMD_805")
      (description "Resistor")
      (fields (field (name "ALTIUM_VALUE") "1K") (field (name "PUBLISHER") "Altium Limited"))
      (libsource (lib "Miscellaneous Devices") (part "Res1"))
    )
    (comp (ref "R15")
      (value "Res1")
      (footprint "SMD_805")
      (description "Resistor")
      (fields (field (name "ALTIUM_VALUE") "10k") (field (name "PUBLISHER") "Altium Limited"))
      (libsource (lib "Miscellaneous Devices") (part "Res1"))
    )
    (comp (ref "R16")
      (value "Res1")
      (footprint "SMD_805")
      (description "Resistor")
      (fields (field (name "ALTIUM_VALUE") "2K") (field (name "PUBLISHER") "Altium Limited"))
      (libsource (lib "Miscellaneous Devices") (part "Res1"))
    )
    (comp (ref "R17")
      (value "Res1")
      (footprint "SMD_805")
      (description "Resistor")
      (fields (field (name "ALTIUM_VALUE") "4K") (field (name "PUBLISHER") "Altium Limited"))
      (libsource (lib "Miscellaneous Devices") (part "Res1"))
    )
    (comp (ref "R18")
      (value "Res1")
      (footprint "SMD_805")
      (description "Resistor")
      (fields (field (name "ALTIUM_VALUE") "2.2k") (field (name "PUBLISHER") "Altium Limited"))
      (libsource (lib "Miscellaneous Devices") (part "Res1"))
    )
    (comp (ref "R19")
      (value "Res1")
      (footprint "SMD_805")
      (description "Resistor")
      (fields (field (name "ALTIUM_VALUE") "2.2k") (field (name "PUBLISHER") "Altium Limited"))
      (libsource (lib "Miscellaneous Devices") (part "Res1"))
    )
    (comp (ref "R20")
      (value "Res1")
      (footprint "SMD_805")
      (description "Resistor")
      (fields (field (name "ALTIUM_VALUE") "2.2k") (field (name "PUBLISHER") "Altium Limited"))
      (libsource (lib "Miscellaneous Devices") (part "Res1"))
    )
    (comp (ref "R21")
      (value "Res1")
      (footprint "SMD_805")
      (description "Resistor")
      (fields (field (name "ALTIUM_VALUE") "2.2k") (field (name "PUBLISHER") "Altium Limited"))
      (libsource (lib "Miscellaneous Devices") (part "Res1"))
    )
    (comp (ref "R22")
      (value "Res1")
      (footprint "SMD_805")
      (description "Resistor")
      (fields (field (name "ALTIUM_VALUE") "1.5K") (field (name "PUBLISHER") "Altium Limited"))
      (libsource (lib "Miscellaneous Devices") (part "Res1"))
    )
    (comp (ref "R23")
      (value "Res1")
      (footprint "SMD_805")
      (description "Resistor")
      (fields (field (name "ALTIUM_VALUE") "100") (field (name "PUBLISHER") "Altium Limited"))
      (libsource (lib "Miscellaneous Devices") (part "Res1"))
    )
    (comp (ref "R24")
      (value "Res1")
      (footprint "SMD_805")
      (description "Resistor")
      (fields (field (name "ALTIUM_VALUE") "100") (field (name "PUBLISHER") "Altium Limited"))
      (libsource (lib "Miscellaneous Devices") (part "Res1"))
    )
    (comp (ref "R25")
      (value "Res1")
      (footprint "SMD_805")
      (description "Resistor")
      (fields (field (name "ALTIUM_VALUE") "1.5K") (field (name "PUBLISHER") "Altium Limited"))
      (libsource (lib "Miscellaneous Devices") (part "Res1"))
    )
    (comp (ref "R26")
      (value "Res1")
      (footprint "SMD_805")
      (description "Resistor")
      (fields (field (name "ALTIUM_VALUE") "10K") (field (name "PUBLISHER") "Altium Limited"))
      (libsource (lib "Miscellaneous Devices") (part "Res1"))
    )
    (comp (ref "R27")
      (value "Res1")
      (footprint "SMD_805")
      (description "Resistor")
      (fields (field (name "ALTIUM_VALUE") "10K") (field (name "PUBLISHER") "Altium Limited"))
      (libsource (lib "Miscellaneous Devices") (part "Res1"))
    )
    (comp (ref "R28")
      (value "Res1")
      (footprint "SMD_805")
      (description "Resistor")
      (fields (field (name "ALTIUM_VALUE") "1K") (field (name "PUBLISHER") "Altium Limited"))
      (libsource (lib "Miscellaneous Devices") (part "Res1"))
    )
    (comp (ref "R29")
      (value "Res1")
      (footprint "SMD_805")
      (description "Resistor")
      (fields (field (name "ALTIUM_VALUE") "27") (field (name "PUBLISHER") "Altium Limited"))
      (libsource (lib "Miscellaneous Devices") (part "Res1"))
    )
    (comp (ref "R30")
      (value "RPot")
      (footprint "VR5")
      (description "Potentiometer")
      (fields (field (name "ALTIUM_VALUE") "1K") (field (name "PUBLISHER") "Altium Limited"))
      (libsource (lib "Miscellaneous Devices") (part "RPot"))
    )
    (comp (ref "R31")
      (value "Res1")
      (footprint "SMD_805")
      (description "Resistor")
      (fields (field (name "ALTIUM_VALUE") "27") (field (name "PUBLISHER") "Altium Limited"))
      (libsource (lib "Miscellaneous Devices") (part "Res1"))
    )
    (comp (ref "R32")
      (value "Res1")
      (footprint "SMD_805")
      (description "Resistor")
      (fields (field (name "ALTIUM_VALUE") "1k") (field (name "PUBLISHER") "Altium Limited"))
      (libsource (lib "Miscellaneous Devices") (part "Res1"))
    )
    (comp (ref "R33")
      (value "Res1")
      (footprint "SMD_805")
      (description "Resistor")
      (fields (field (name "ALTIUM_VALUE") "2K") (field (name "PUBLISHER") "Altium Limited"))
      (libsource (lib "Miscellaneous Devices") (part "Res1"))
    )
    (comp (ref "R34")
      (value "Res1")
      (footprint "SMD_805")
      (description "Resistor")
      (fields (field (name "ALTIUM_VALUE") "12k") (field (name "PUBLISHER") "Altium Limited"))
      (libsource (lib "Miscellaneous Devices") (part "Res1"))
    )
    (comp (ref "R35")
      (value "Res1")
      (footprint "SMD_805")
      (description "Resistor")
      (fields (field (name "ALTIUM_VALUE") "100") (field (name "PUBLISHER") "Altium Limited"))
      (libsource (lib "Miscellaneous Devices") (part "Res1"))
    )
    (comp (ref "R36")
      (value "Res1")
      (footprint "SMD_805")
      (description "Resistor")
      (fields (field (name "ALTIUM_VALUE") "4.7k") (field (name "PUBLISHER") "Altium Limited"))
      (libsource (lib "Miscellaneous Devices") (part "Res1"))
    )
    (comp (ref "R37")
      (value "Res1")
      (footprint "SMD_805")
      (description "Resistor")
      (fields (field (name "ALTIUM_VALUE") "4.7k") (field (name "PUBLISHER") "Altium Limited"))
      (libsource (lib "Miscellaneous Devices") (part "Res1"))
    )
    (comp (ref "R38")
      (value "Res1")
      (footprint "SMD_805")
      (description "Resistor")
      (fields (field (name "ALTIUM_VALUE") "4.7K") (field (name "PUBLISHER") "Altium Limited"))
      (libsource (lib "Miscellaneous Devices") (part "Res1"))
    )
    (comp (ref "R39")
      (value "Res1")
      (footprint "SMD_805")
      (description "Resistor")
      (fields (field (name "ALTIUM_VALUE") "10K") (field (name "PUBLISHER") "Altium Limited"))
      (libsource (lib "Miscellaneous Devices") (part "Res1"))
    )
    (comp (ref "R40")
      (value "Res1")
      (footprint "SMD_805")
      (description "Resistor")
      (fields (field (name "ALTIUM_VALUE") "2.2k") (field (name "PUBLISHER") "Altium Limited"))
      (libsource (lib "Miscellaneous Devices") (part "Res1"))
    )
    (comp (ref "R41")
      (value "Res1")
      (footprint "SMD_805")
      (description "Resistor")
      (fields (field (name "ALTIUM_VALUE") "100") (field (name "PUBLISHER") "Altium Limited"))
      (libsource (lib "Miscellaneous Devices") (part "Res1"))
    )
    (comp (ref "R42")
      (value "Res1")
      (footprint "SMD_805")
      (description "Resistor")
      (fields (field (name "ALTIUM_VALUE") "100") (field (name "PUBLISHER") "Altium Limited"))
      (libsource (lib "Miscellaneous Devices") (part "Res1"))
    )
    (comp (ref "R43")
      (value "Res1")
      (footprint "SMD_805")
      (description "Resistor")
      (fields (field (name "ALTIUM_VALUE") "4.7k") (field (name "PUBLISHER") "Altium Limited"))
      (libsource (lib "Miscellaneous Devices") (part "Res1"))
    )
    (comp (ref "R44")
      (value "Res1")
      (footprint "SMD_805")
      (description "Resistor")
      (fields (field (name "ALTIUM_VALUE") "4.7k") (field (name "PUBLISHER") "Altium Limited"))
      (libsource (lib "Miscellaneous Devices") (part "Res1"))
    )
    (comp (ref "R45")
      (value "Res1")
      (footprint "SMD_805")
      (description "Resistor")
      (fields (field (name "ALTIUM_VALUE") "100") (field (name "PUBLISHER") "Altium Limited"))
      (libsource (lib "Miscellaneous Devices") (part "Res1"))
    )
    (comp (ref "R46")
      (value "Res1")
      (footprint "SMD_805")
      (description "Resistor")
      (fields (field (name "ALTIUM_VALUE") "10K") (field (name "PUBLISHER") "Altium Limited"))
      (libsource (lib "Miscellaneous Devices") (part "Res1"))
    )
    (comp (ref "R47")
      (value "Res1")
      (footprint "SMD_805")
      (description "Resistor")
      (fields (field (name "ALTIUM_VALUE") "10K") (field (name "PUBLISHER") "Altium Limited"))
      (libsource (lib "Miscellaneous Devices") (part "Res1"))
    )
    (comp (ref "S1")
      (value "SW DIP-8")
      (footprint "ARRAY_KEY8")
      (description "DIP Switch, 8 Position, SPST")
      (fields (field (name "PUBLISHER") "Altium Limited"))
      (libsource (lib "Miscellaneous Devices") (part "SW DIP-8"))
    )
    (comp (ref "S2")
      (value "SW-PB")
      (footprint "RES_B")
      (description "Switch")
      (fields (field (name "PUBLISHER") "Altium Limited"))
      (libsource (lib "Miscellaneous Devices") (part "SW-PB"))
    )
    (comp (ref "S3")
      (value "SW-PB")
      (footprint "RES_B")
      (description "Switch")
      (fields (field (name "PUBLISHER") "Altium Limited"))
      (libsource (lib "Miscellaneous Devices") (part "SW-PB"))
    )
    (comp (ref "S4")
      (value "SW-PB")
      (footprint "RES_B")
      (description "Switch")
      (fields (field (name "PUBLISHER") "Altium Limited"))
      (libsource (lib "Miscellaneous Devices") (part "SW-PB"))
    )
    (comp (ref "S5")
      (value "SW-PB")
      (footprint "RES_B")
      (description "Switch")
      (fields (field (name "PUBLISHER") "Altium Limited"))
      (libsource (lib "Miscellaneous Devices") (part "SW-PB"))
    )
    (comp (ref "S6")
      (value "SW-SPST")
      (footprint "KEY1")
      (description "Single-Pole, Single-Throw Switch")
      (fields (field (name "PUBLISHER") "Altium Limited"))
      (libsource (lib "Miscellaneous Devices") (part "SW-SPST"))
    )
    (comp (ref "S7")
      (value "SW-PB")
      (footprint "SPST-2")
      (description "Switch")
      (fields (field (name "PUBLISHER") "Altium Limited"))
      (libsource (lib "Miscellaneous Devices") (part "SW-PB"))
    )
    (comp (ref "S8")
      (value "SW-SPST")
      (footprint "SPST-2")
      (description "Single-Pole, Single-Throw Switch")
      (fields (field (name "PUBLISHER") "Altium Limited"))
      (libsource (lib "Miscellaneous Devices") (part "SW-SPST"))
    )
    (comp (ref "S9")
      (value "SW-PB")
      (footprint "SPST-2")
      (description "Switch")
      (fields (field (name "PUBLISHER") "Altium Limited"))
      (libsource (lib "Miscellaneous Devices") (part "SW-PB"))
    )
    (comp (ref "U1") (value "FT232RL") (footprint "SOP28") (libsource (lib "FT232RL") (part "FT232RL")))
    (comp (ref "U2")
      (value "IS61LV25616AL")
      (footprint "SOP44")
      (libsource (lib "IS61LV25616AL") (part "IS61LV25616AL"))
    )
    (comp (ref "U3")
      (value "XC3S400-4PQ208C")
      (footprint "XC3S400_PQ208")
      (description "Spartan-3 1.2V FPGA, 141 User I/Os, 208-Pin PQFP, Standard Performance, Commercial Grade")
      (fields (field (name "PUBLISHER") "Altium Limited"))
      (libsource (lib "Xilinx Spartan-3") (part "XC3S400-4PQ208C"))
    )
    (comp (ref "U4")
      (value "LD1117DT33")
      (footprint "SOT223")
      (libsource (lib "LD1117DT33") (part "Component_1"))
    )
    (comp (ref "U5")
      (value "LD1117DT33")
      (footprint "SOT223")
      (libsource (lib "LD1117DT33") (part "Component_1"))
    )
    (comp (ref "U6")
      (value "LD1117DT33")
      (footprint "SOT223")
      (libsource (lib "LD1117DT33") (part "Component_1"))
    )
    (comp (ref "U7")
      (value "LD1117DT33")
      (footprint "SOT223")
      (libsource (lib "LD1117DT33") (part "Component_1"))
    )
    (comp (ref "U8")
      (value "STM32F103RBT6")
      (footprint "PQFP64")
      (description "STM32 ARM-based 32-bit MCU with 128 Kbytes Flash, 64-pin LQFP, Industrial Temperature")
      (fields (field (name "PUBLISHER") "Altium Limited"))
      (libsource (lib "altium-import") (part "root_0_STM32F103RBT6_"))
    )
    (comp (ref "U9")
      (value "FT2232HL-Reel")
      (footprint "LQFP64")
      (description "Dual High Speed USB To Multipurpose UART/FIFO IC, 64-pin LQFP, Tape and Reel")
      (fields (field (name "MANUFACTURER") "FTDI"))
      (libsource (lib "FTDI FT Series") (part "FT2232HL-Reel"))
    )
    (comp (ref "U10")
      (value "LM2576HVT-5.0")
      (footprint "LM2576_SMD")
      (description "SIMPLE SWITCHER; 3A Step-Down Voltage Regulator")
      (fields
        (field (name "MANUFACTURER") "National Semiconductor")
        (field (name "DIGIKEYPARTNUMBER") "LM2576HVT-5.0-ND")
        (field (name "PUBLISHER") "Altium Limited")
      )
      (libsource (lib "NSC Switcher") (part "LM2576HVT-5.0"))
    )
    (comp (ref "U11")
      (value "93LC46A-E/SN")
      (footprint "SOIC127P600X175-8N")
      (description "1K, 128x8-bit, 2.5V Microwire Serial EEPROM, 8-Pin SOIC 150mil, Extended Temperature")
      (fields (field (name "PUBLISHER") "Altium Limited"))
      (libsource (lib "Microchip EEPROM Microwire Serial") (part "93LC46A-E/SN"))
    )
    (comp (ref "U12")
      (value "XCF02SVO20C")
      (footprint "XCF02S")
      (fields (field (name "PUBLISHER") "Altium Limited"))
      (libsource (lib "altium-import") (part "root_0_mirrored_XCF02SVO20C_"))
    )
    (comp (ref "U13") (value "24C512") (footprint "SOP8") (libsource (lib "EE_24C512") (part "24C512")))
    (comp (ref "U14")
      (value "MAX3232CPE")
      (footprint "SOP16")
      (description "3.0V TO 5.5V, Low-Power, up to 1Mbps, True RS-232 Transceiver Using Four 0.1µF External Capacitor")
      (fields (field (name "PUBLISHER") "Altium Limited"))
      (libsource (lib "altium-import") (part "root_0_MAX3232CPE_"))
    )
    (comp (ref "USB1")
      (value "MICRO_USB")
      (footprint "MINI_USB_NEW")
      (libsource (lib "MICRO_USB") (part "MICRO_USB"))
    )
    (comp (ref "USB2")
      (value "MICRO_USB")
      (footprint "MINI_USB_NEW")
      (libsource (lib "MICRO_USB") (part "MICRO_USB"))
    )
    (comp (ref "VGA1")
      (value "Connector 15")
      (footprint "VGA_PORT")
      (description "Receptacle Assembly, 15-Pin, Sim Line Connector")
      (fields (field (name "PUBLISHER") "Altium Limited"))
      (libsource (lib "Miscellaneous Connectors") (part "Connector 15"))
    )
    (comp (ref "Y1")
      (value "14.7456 MHz")
      (footprint "BC557")
      (description "Crystal Oscillator")
      (fields (field (name "PUBLISHER") "Altium Limited"))
      (libsource (lib "Miscellaneous Devices") (part "XTAL"))
    )
    (comp (ref "Y2")
      (value "12 MHz")
      (footprint "XTAL_SMD")
      (description "Crystal Oscillator")
      (fields (field (name "PUBLISHER") "Altium Limited"))
      (libsource (lib "Miscellaneous Devices") (part "XTAL"))
    )
  )
  (nets
    (net (code "1") (name "/A0") (class "Default")
      (node (ref "U2") (pin "1") (pinfunction "A0_1") (pintype "passive"))
      (node (ref "U3") (pin "183") (pinfunction "IO_L32P_0/GCLK6_183") (pintype "bidirectional"))
    )
    (net (code "2") (name "/A1") (class "Default")
      (node (ref "U2") (pin "2") (pinfunction "A1_2") (pintype "passive"))
      (node (ref "U3") (pin "182") (pinfunction "IO_182") (pintype "bidirectional"))
    )
    (net (code "3") (name "/A2") (class "Default")
      (node (ref "U2") (pin "3") (pinfunction "A2_3") (pintype "passive"))
      (node (ref "U3") (pin "181") (pinfunction "IO_L32N_1/GCLK5_181") (pintype "bidirectional"))
    )
    (net (code "4") (name "/A3") (class "Default")
      (node (ref "U2") (pin "4") (pinfunction "A3_4") (pintype "passive"))
      (node (ref "U3") (pin "180") (pinfunction "IO_L32P_1/GCLK4_180") (pintype "bidirectional"))
    )
    (net (code "5") (name "/A4") (class "Default")
      (node (ref "U2") (pin "5") (pinfunction "A4_5") (pintype "passive"))
      (node (ref "U3") (pin "178") (pinfunction "IO_L31N_1/VREF_1_178") (pintype "bidirectional"))
    )
    (net (code "6") (name "/A5") (class "Default")
      (node (ref "U2") (pin "18") (pinfunction "A5_18") (pintype "passive"))
      (node (ref "U3") (pin "161") (pinfunction "IO_L01P_1/VRN_1_161") (pintype "bidirectional"))
    )
    (net (code "7") (name "/A6") (class "Default")
      (node (ref "U2") (pin "19") (pinfunction "A6_19") (pintype "passive"))
      (node (ref "U3") (pin "156") (pinfunction "IO_L01N_2/VRP_2_156") (pintype "bidirectional"))
    )
    (net (code "8") (name "/A7") (class "Default")
      (node (ref "U2") (pin "20") (pinfunction "A7_20") (pintype "passive"))
      (node (ref "U3") (pin "155") (pinfunction "IO_L01P_2/VRN_2_155") (pintype "bidirectional"))
    )
    (net (code "9") (name "/A8") (class "Default")
      (node (ref "U2") (pin "21") (pinfunction "A8_21") (pintype "passive"))
      (node (ref "U3") (pin "154") (pinfunction "IO/VREF_2_154") (pintype "bidirectional"))
    )
    (net (code "10") (name "/A9") (class "Default")
      (node (ref "U2") (pin "22") (pinfunction "A9_22") (pintype "passive"))
      (node (ref "U3") (pin "152") (pinfunction "IO_L19N_2_152") (pintype "bidirectional"))
    )
    (net (code "11") (name "/A10") (class "Default")
      (node (ref "U2") (pin "23") (pinfunction "A10_23") (pintype "passive"))
      (node (ref "U3") (pin "5") (pinfunction "IO_L16N_7_5") (pintype "bidirectional"))
    )
    (net (code "12") (name "/A11") (class "Default")
      (node (ref "U2") (pin "24") (pinfunction "A11_24") (pintype "passive"))
      (node (ref "U3") (pin "4") (pinfunction "IO_L16P_7/VREF_7_4") (pintype "bidirectional"))
    )
    (net (code "13") (name "/A12") (class "Default")
      (node (ref "U2") (pin "25") (pinfunction "A12_25") (pintype "passive"))
      (node (ref "U3") (pin "3") (pinfunction "IO_L01N_7/VRP_7_3") (pintype "bidirectional"))
    )
    (net (code "14") (name "/A13") (class "Default")
      (node (ref "U2") (pin "26") (pinfunction "A13_26") (pintype "passive"))
      (node (ref "U3") (pin "2") (pinfunction "IO_L01P_7/VRN_7_2") (pintype "bidirectional"))
    )
    (net (code "15") (name "/A14") (class "Default")
      (node (ref "U2") (pin "27") (pinfunction "A14_27") (pintype "passive"))
      (node (ref "U3") (pin "205") (pinfunction "IO/VREF_0_205") (pintype "bidirectional"))
    )
    (net (code "16") (name "/A15") (class "Default")
      (node (ref "U2") (pin "42") (pinfunction "A15_42") (pintype "passive"))
      (node (ref "U3") (pin "187") (pinfunction "IO_L31N_0_187") (pintype "bidirectional"))
    )
    (net (code "17") (name "/A16") (class "Default")
      (node (ref "U2") (pin "43") (pinfunction "A16_43") (pintype "passive"))
      (node (ref "U3") (pin "185") (pinfunction "IO_L31P_0/VREF_0_185") (pintype "bidirectional"))
    )
    (net (code "18") (name "/A17") (class "Default")
      (node (ref "U2") (pin "44") (pinfunction "A17_44") (pintype "passive"))
      (node (ref "U3") (pin "184") (pinfunction "IO_L32N_0/GCLK7_184") (pintype "bidirectional"))
    )
    (net (code "19") (name "/BLUE0") (class "Default")
      (node (ref "R6") (pin "2") (pinfunction "2_2") (pintype "passive"))
      (node (ref "U3") (pin "64") (pinfunction "IO_L27P_5_64") (pintype "bidirectional"))
    )
    (net (code "20") (name "/BLUE1") (class "Default")
      (node (ref "R5") (pin "2") (pinfunction "2_2") (pintype "passive"))
      (node (ref "U3") (pin "63") (pinfunction "IO_63") (pintype "bidirectional"))
    )
    (net (code "21") (name "/BLUE2") (class "Default")
      (node (ref "R4") (pin "2") (pinfunction "2_2") (pintype "passive"))
      (node (ref "U3") (pin "62") (pinfunction "IO_L10N_5/VRP_5_62") (pintype "bidirectional"))
    )
    (net (code "22") (name "/BLUE3") (class "Default")
      (node (ref "R3") (pin "2") (pinfunction "2_2") (pintype "passive"))
      (node (ref "U3") (pin "61") (pinfunction "IO_L10P_5/VRN_5_61") (pintype "bidirectional"))
    )
    (net (code "23") (name "/BOOT0") (class "Default")
      (node (ref "R47") (pin "2") (pinfunction "2_2") (pintype "passive"))
      (node (ref "S8") (pin "2") (pinfunction "NO_2") (pintype "passive"))
      (node (ref "U8") (pin "60") (pinfunction "BOOT0_60") (pintype "input"))
    )
    (net (code "24") (name "/BUT_RISE1") (class "Default")
      (node (ref "C8") (pin "1") (pinfunction "1_1") (pintype "passive"))
      (node (ref "R18") (pin "2") (pinfunction "2_2") (pintype "passive"))
      (node (ref "S2") (pin "1") (pinfunction "1_1") (pintype "passive"))
      (node (ref "U3") (pin "45") (pinfunction "IO_L20N_6_45") (pintype "bidirectional"))
    )
    (net (code "25") (name "/BUT_RISE2") (class "Default")
      (node (ref "C9") (pin "1") (pinfunction "1_1") (pintype "passive"))
      (node (ref "R19") (pin "2") (pinfunction "2_2") (pintype "passive"))
      (node (ref "S3") (pin "1") (pinfunction "1_1") (pintype "passive"))
      (node (ref "U3") (pin "46") (pinfunction "IO_L19P_6_46") (pintype "bidirectional"))
    )
    (net (code "26") (name "/BUT_RISE3") (class "Default")
      (node (ref "C10") (pin "1") (pinfunction "1_1") (pintype "passive"))
      (node (ref "R20") (pin "2") (pinfunction "2_2") (pintype "passive"))
      (node (ref "S4") (pin "1") (pinfunction "1_1") (pintype "passive"))
      (node (ref "U8") (pin "14") (pinfunction "PA0-WKUP_14") (pintype "bidirectional"))
    )
    (net (code "27") (name "/BUT_RISE4") (class "Default")
      (node (ref "C11") (pin "1") (pinfunction "1_1") (pintype "passive"))
      (node (ref "R21") (pin "2") (pinfunction "2_2") (pintype "passive"))
      (node (ref "S5") (pin "1") (pinfunction "1_1") (pintype "passive"))
      (node (ref "U8") (pin "15") (pinfunction "PA1_15") (pintype "bidirectional"))
    )
    (net (code "28") (name "/CE") (class "Default")
      (node (ref "U2") (pin "6") (pinfunction "~{CE}_6") (pintype "passive"))
      (node (ref "U3") (pin "176") (pinfunction "IO_L31P_1_176") (pintype "bidirectional"))
    )
    (net (code "29") (name "/D4") (class "Default")
      (node (ref "LCD1") (pin "11") (pinfunction "D4_11") (pintype "passive"))
      (node (ref "U8") (pin "36") (pinfunction "PB15_36") (pintype "bidirectional"))
    )
    (net (code "30") (name "/D5") (class "Default")
      (node (ref "LCD1") (pin "12") (pinfunction "D5_12") (pintype "passive"))
      (node (ref "U8") (pin "35") (pinfunction "PB14_35") (pintype "bidirectional"))
    )
    (net (code "31") (name "/D6") (class "Default")
      (node (ref "LCD1") (pin "13") (pinfunction "D6_13") (pintype "passive"))
      (node (ref "U8") (pin "34") (pinfunction "PB13_34") (pintype "bidirectional"))
    )
    (net (code "32") (name "/D7") (class "Default")
      (node (ref "LCD1") (pin "14") (pinfunction "D7_14") (pintype "passive"))
      (node (ref "U8") (pin "33") (pinfunction "PB12_33") (pintype "bidirectional"))
    )
    (net (code "33") (name "/DIN_92") (class "Default")
      (node (ref "U12") (pin "1") (pinfunction "D0_1") (pintype "tri_state"))
      (node (ref "U3") (pin "92") (pinfunction "IO_L27N_4/DIN/D0_92") (pintype "bidirectional"))
    )
    (net (code "34") (name "/E") (class "Default")
      (node (ref "LCD1") (pin "6") (pinfunction "E_6") (pintype "passive"))
      (node (ref "U8") (pin "37") (pinfunction "PC6_37") (pintype "bidirectional"))
    )
    (net (code "35") (name "/FTOU") (class "Default")
      (node (ref "U3") (pin "101") (pinfunction "IO_L01N_4/VRP_4_101") (pintype "bidirectional"))
      (node (ref "U8") (pin "61") (pinfunction "PB8_61") (pintype "bidirectional"))
    )
    (net (code "36") (name "/GREEN0") (class "Default")
      (node (ref "R12") (pin "2") (pinfunction "2_2") (pintype "passive"))
      (node (ref "U3") (pin "71") (pinfunction "IO_71") (pintype "bidirectional"))
    )
    (net (code "37") (name "/GREEN1") (class "Default")
      (node (ref "R11") (pin "2") (pinfunction "2_2") (pintype "passive"))
      (node (ref "U3") (pin "68") (pinfunction "IO_L28N_5/D6_68") (pintype "bidirectional"))
    )
    (net (code "38") (name "/GREEN2") (class "Default")
      (node (ref "R10") (pin "2") (pinfunction "2_2") (pintype "passive"))
      (node (ref "U3") (pin "67") (pinfunction "IO_L28P_5/D7_67") (pintype "bidirectional"))
    )
    (net (code "39") (name "/GREEN3") (class "Default")
      (node (ref "R9") (pin "2") (pinfunction "2_2") (pintype "passive"))
      (node (ref "U3") (pin "65") (pinfunction "IO_L27N_5/VREF_5_65") (pintype "bidirectional"))
    )
    (net (code "40") (name "/HSYNC") (class "Default")
      (node (ref "R1") (pin "2") (pinfunction "2_2") (pintype "passive"))
      (node (ref "U3") (pin "57") (pinfunction "IO_L01P_5/CS_B_57") (pintype "bidirectional"))
    )
    (net (code "41") (name "/INIT_B_83") (class "Default")
      (node (ref "R38") (pin "1") (pinfunction "1_1") (pintype "passive"))
      (node (ref "U12") (pin "8") (pinfunction "OE/~{RESET}_8") (pintype "bidirectional"))
      (node (ref "U3") (pin "83") (pinfunction "IO_L31N_4/INIT_B_83") (pintype "bidirectional"))
    )
    (net (code "42") (name "/IO0") (class "Default")
      (node (ref "U2") (pin "7") (pinfunction "I/O0_7") (pintype "passive"))
      (node (ref "U3") (pin "175") (pinfunction "IO_175") (pintype "bidirectional"))
    )
    (net (code "43") (name "/IO1") (class "Default")
      (node (ref "U2") (pin "8") (pinfunction "I/O1_8") (pintype "passive"))
      (node (ref "U3") (pin "172") (pinfunction "IO_L28N_1_172") (pintype "bidirectional"))
    )
    (net (code "44") (name "/IO2") (class "Default")
      (node (ref "U2") (pin "9") (pinfunction "I/O2_9") (pintype "passive"))
      (node (ref "U3") (pin "171") (pinfunction "IO_L28P_1_171") (pintype "bidirectional"))
    )
    (net (code "45") (name "/IO3") (class "Default")
      (node (ref "U2") (pin "10") (pinfunction "I/O3_10") (pintype "passive"))
      (node (ref "U3") (pin "169") (pinfunction "IO_L27N_1_169") (pintype "bidirectional"))
    )
    (net (code "46") (name "/IO4") (class "Default")
      (node (ref "U2") (pin "13") (pinfunction "I/O4_13") (pintype "passive"))
      (node (ref "U3") (pin "168") (pinfunction "IO_L27P_1_168") (pintype "bidirectional"))
    )
    (net (code "47") (name "/IO5") (class "Default")
      (node (ref "U2") (pin "14") (pinfunction "I/O5_14") (pintype "passive"))
      (node (ref "U3") (pin "167") (pinfunction "IO_167") (pintype "bidirectional"))
    )
    (net (code "48") (name "/IO6") (class "Default")
      (node (ref "U2") (pin "15") (pinfunction "I/O6_15") (pintype "passive"))
      (node (ref "U3") (pin "166") (pinfunction "IO_L10N_1/VREF_1_166") (pintype "bidirectional"))
    )
    (net (code "49") (name "/IO7") (class "Default")
      (node (ref "U2") (pin "16") (pinfunction "I/O7_16") (pintype "passive"))
      (node (ref "U3") (pin "165") (pinfunction "IO_L10P_1_165") (pintype "bidirectional"))
    )
    (net (code "50") (name "/IO8") (class "Default")
      (node (ref "U2") (pin "29") (pinfunction "I/O8_29") (pintype "passive"))
      (node (ref "U3") (pin "204") (pinfunction "IO_L01N_0/VRP_0_204") (pintype "bidirectional"))
    )
    (net (code "51") (name "/IO9") (class "Default")
      (node (ref "U2") (pin "30") (pinfunction "I/O9_30") (pintype "passive"))
      (node (ref "U3") (pin "203") (pinfunction "IO_L01P_0/VRN_0_203") (pintype "bidirectional"))
    )
    (net (code "52") (name "/IO10") (class "Default")
      (node (ref "U2") (pin "31") (pinfunction "I/O10_31") (pintype "passive"))
      (node (ref "U3") (pin "200") (pinfunction "IO/VREF_0_200") (pintype "bidirectional"))
    )
    (net (code "53") (name "/IO11") (class "Default")
      (node (ref "U2") (pin "32") (pinfunction "I/O11_32") (pintype "passive"))
      (node (ref "U3") (pin "199") (pinfunction "IO_L25N_0_199") (pintype "bidirectional"))
    )
    (net (code "54") (name "/IO12") (class "Default")
      (node (ref "U2") (pin "35") (pinfunction "I/O12_35") (pintype "passive"))
      (node (ref "U3") (pin "198") (pinfunction "IO_L25P_0_198") (pintype "bidirectional"))
    )
    (net (code "55") (name "/IO13") (class "Default")
      (node (ref "U2") (pin "36") (pinfunction "I/O13_36") (pintype "passive"))
      (node (ref "U3") (pin "197") (pinfunction "IO_197") (pintype "bidirectional"))
    )
    (net (code "56") (name "/IO14") (class "Default")
      (node (ref "U2") (pin "37") (pinfunction "I/O14_37") (pintype "passive"))
      (node (ref "U3") (pin "196") (pinfunction "IO_L27N_0_196") (pintype "bidirectional"))
    )
    (net (code "57") (name "/IO15") (class "Default")
      (node (ref "U2") (pin "38") (pinfunction "I/O15_38") (pintype "passive"))
      (node (ref "U3") (pin "194") (pinfunction "IO_L27P_0_194") (pintype "bidirectional"))
    )
    (net (code "58") (name "/I{slash}O_P79_GCLK0") (class "Default")
      (node (ref "OSC1") (pin "3") (pinfunction "OUT_3") (pintype "passive"))
      (node (ref "U3") (pin "79") (pinfunction "IO_L32P_4/GCLK0_79") (pintype "bidirectional"))
    )
    (net (code "59") (name "/K_1") (class "Default")
      (node (ref "*") (pin "1") (pinfunction "1_1") (pintype "passive"))
      (node (ref "S1") (pin "1") (pinfunction "A1_1") (pintype "passive"))
      (node (ref "U3") (pin "19") (pinfunction "IO_L23N_7_19") (pintype "bidirectional"))
    )
    (net (code "60") (name "/K_2") (class "Default")
      (node (ref "*") (pin "2") (pinfunction "2_2") (pintype "passive"))
      (node (ref "S1") (pin "2") (pinfunction "A2_2") (pintype "passive"))
      (node (ref "U3") (pin "18") (pinfunction "IO_L23P_7_18") (pintype "bidirectional"))
    )
    (net (code "61") (name "/K_3") (class "Default")
      (node (ref "*") (pin "3") (pinfunction "3_3") (pintype "passive"))
      (node (ref "S1") (pin "3") (pinfunction "A3_3") (pintype "passive"))
      (node (ref "U3") (pin "16") (pinfunction "IO_L22N_7_16") (pintype "bidirectional"))
    )
    (net (code "62") (name "/K_4") (class "Default")
      (node (ref "*") (pin "4") (pinfunction "4_4") (pintype "passive"))
      (node (ref "S1") (pin "4") (pinfunction "A4_4") (pintype "passive"))
      (node (ref "U3") (pin "15") (pinfunction "IO_L22P_7_15") (pintype "bidirectional"))
    )
    (net (code "63") (name "/K_5") (class "Default")
      (node (ref "*") (pin "5") (pinfunction "5_5") (pintype "passive"))
      (node (ref "S1") (pin "5") (pinfunction "A5_5") (pintype "passive"))
      (node (ref "U3") (pin "13") (pinfunction "IO_L21N_7_13") (pintype "bidirectional"))
    )
    (net (code "64") (name "/K_6") (class "Default")
      (node (ref "*") (pin "6") (pinfunction "6_6") (pintype "passive"))
      (node (ref "S1") (pin "6") (pinfunction "A6_6") (pintype "passive"))
      (node (ref "U3") (pin "12") (pinfunction "IO_L21P_7_12") (pintype "bidirectional"))
    )
    (net (code "65") (name "/K_7") (class "Default")
      (node (ref "*") (pin "7") (pinfunction "7_7") (pintype "passive"))
      (node (ref "S1") (pin "7") (pinfunction "A7_7") (pintype "passive"))
      (node (ref "U3") (pin "11") (pinfunction "IO_L20N_7_11") (pintype "bidirectional"))
    )
    (net (code "66") (name "/K_8") (class "Default")
      (node (ref "*") (pin "8") (pinfunction "8_8") (pintype "passive"))
      (node (ref "S1") (pin "8") (pinfunction "A8_8") (pintype "passive"))
      (node (ref "U3") (pin "10") (pinfunction "IO_L20P_7_10") (pintype "bidirectional"))
    )
    (net (code "67") (name "/LB") (class "Default")
      (node (ref "U2") (pin "39") (pinfunction "~{LB}_39") (pintype "passive"))
      (node (ref "U3") (pin "191") (pinfunction "IO_L30N_0_191") (pintype "bidirectional"))
    )
    (net (code "68") (name "/NRST") (class "Default")
      (node (ref "C43") (pin "2") (pinfunction "2_2") (pintype "passive"))
      (node (ref "P2") (pin "3") (pinfunction "3_3") (pintype "passive"))
      (node (ref "R46") (pin "1") (pinfunction "1_1") (pintype "passive"))
      (node (ref "S9") (pin "2") (pinfunction "2_2") (pintype "passive"))
      (node (ref "U8") (pin "7") (pinfunction "NRST_7") (pintype "bidirectional"))
    )
    (net (code "69") (name "/OE") (class "Default")
      (node (ref "U2") (pin "41") (pinfunction "~{OE}_41") (pintype "passive"))
      (node (ref "U3") (pin "189") (pinfunction "IO_189") (pintype "bidirectional"))
    )
    (net (code "70") (name "/OSC_IN") (class "Default")
      (node (ref "C32") (pin "2") (pinfunction "2_2") (pintype "passive"))
      (node (ref "U8") (pin "5") (pinfunction "OSC_IN/PD0_5") (pintype "input"))
      (node (ref "Y1") (pin "2") (pinfunction "OSC2_2") (pintype "passive"))
    )
    (net (code "71") (name "/OSC_OUT") (class "Default")
      (node (ref "C34") (pin "2") (pinfunction "2_2") (pintype "passive"))
      (node (ref "U8") (pin "6") (pinfunction "OSC_OUT/PD1_6") (pintype "output"))
      (node (ref "Y1") (pin "1") (pinfunction "OSC1_1") (pintype "passive"))
    )
    (net (code "72") (name "/P1") (class "Default")
      (node (ref "P3") (pin "1") (pinfunction "1_1") (pintype "passive"))
      (node (ref "U8") (pin "45") (pinfunction "PA12_45") (pintype "bidirectional"))
    )
    (net (code "73") (name "/P2") (class "Default")
      (node (ref "P3") (pin "7") (pinfunction "7_7") (pintype "passive"))
      (node (ref "U8") (pin "26") (pinfunction "PB0_26") (pintype "bidirectional"))
    )
    (net (code "74") (name "/P3") (class "Default")
      (node (ref "P3") (pin "6") (pinfunction "6_6") (pintype "passive"))
      (node (ref "U8") (pin "27") (pinfunction "PB1_27") (pintype "bidirectional"))
    )
    (net (code "75") (name "/P4") (class "Default")
      (node (ref "P3") (pin "5") (pinfunction "5_5") (pintype "passive"))
      (node (ref "R28") (pin "2") (pinfunction "2_2") (pintype "passive"))
      (node (ref "U8") (pin "28") (pinfunction "PB2/BOOT1_28") (pintype "bidirectional"))
    )
    (net (code "76") (name "/P5") (class "Default")
      (node (ref "P3") (pin "4") (pinfunction "4_4") (pintype "passive"))
      (node (ref "U8") (pin "29") (pinfunction "PB10_29") (pintype "bidirectional"))
    )
    (net (code "77") (name "/P6") (class "Default")
      (node (ref "P3") (pin "3") (pinfunction "3_3") (pintype "passive"))
      (node (ref "U8") (pin "30") (pinfunction "PB11_30") (pintype "bidirectional"))
    )
    (net (code "78") (name "/P7") (class "Default")
      (node (ref "P3") (pin "13") (pinfunction "13_13") (pintype "passive"))
      (node (ref "U8") (pin "8") (pinfunction "PC0_8") (pintype "bidirectional"))
    )
    (net (code "79") (name "/P8") (class "Default")
      (node (ref "P3") (pin "12") (pinfunction "12_12") (pintype "passive"))
      (node (ref "U8") (pin "9") (pinfunction "PC1_9") (pintype "bidirectional"))
    )
    (net (code "80") (name "/P9") (class "Default")
      (node (ref "P3") (pin "11") (pinfunction "11_11") (pintype "passive"))
      (node (ref "U8") (pin "10") (pinfunction "PC2_10") (pintype "bidirectional"))
    )
    (net (code "81") (name "/P10") (class "Default")
      (node (ref "P3") (pin "10") (pinfunction "10_10") (pintype "passive"))
      (node (ref "U8") (pin "11") (pinfunction "PC3_11") (pintype "bidirectional"))
    )
    (net (code "82") (name "/P11") (class "Default")
      (node (ref "P3") (pin "9") (pinfunction "9_9") (pintype "passive"))
      (node (ref "U8") (pin "24") (pinfunction "PC4_24") (pintype "bidirectional"))
    )
    (net (code "83") (name "/P12") (class "Default")
      (node (ref "P3") (pin "8") (pinfunction "8_8") (pintype "passive"))
      (node (ref "U8") (pin "25") (pinfunction "PC5_25") (pintype "bidirectional"))
    )
    (net (code "84") (name "/P13") (class "Default")
      (node (ref "P3") (pin "2") (pinfunction "2_2") (pintype "passive"))
      (node (ref "U8") (pin "40") (pinfunction "PC9_40") (pintype "bidirectional"))
    )
    (net (code "85") (name "/P14") (class "Default")
      (node (ref "P3") (pin "16") (pinfunction "16_16") (pintype "passive"))
      (node (ref "U8") (pin "2") (pinfunction "PC13-TAMPER-RTC_2") (pintype "bidirectional"))
    )
    (net (code "86") (name "/P15") (class "Default")
      (node (ref "P3") (pin "15") (pinfunction "15_15") (pintype "passive"))
      (node (ref "U8") (pin "3") (pinfunction "PC14-OSC32_IN_3") (pintype "bidirectional"))
    )
    (net (code "87") (name "/P16") (class "Default")
      (node (ref "P3") (pin "14") (pinfunction "14_14") (pintype "passive"))
      (node (ref "U8") (pin "4") (pinfunction "PC15-OSC32_OUT_4") (pintype "bidirectional"))
    )
    (net (code "88") (name "/PA2") (class "Default")
      (node (ref "U3") (pin "108") (pinfunction "IO_L17P_3/VREF_3_108") (pintype "bidirectional"))
      (node (ref "U8") (pin "16") (pinfunction "PA2_16") (pintype "bidirectional"))
    )
    (net (code "89") (name "/PA3") (class "Default")
      (node (ref "U3") (pin "107") (pinfunction "IO_L01N_3/VRP_3_107") (pintype "bidirectional"))
      (node (ref "U8") (pin "17") (pinfunction "PA3_17") (pintype "bidirectional"))
    )
    (net (code "90") (name "/PA4") (class "Default")
      (node (ref "U3") (pin "106") (pinfunction "IO_L01P_3/VRN_3_106") (pintype "bidirectional"))
      (node (ref "U8") (pin "20") (pinfunction "PA4_20") (pintype "bidirectional"))
    )
    (net (code "91") (name "/PA5") (class "Default")
      (node (ref "U3") (pin "109") (pinfunction "IO_L17N_3_109") (pintype "bidirectional"))
      (node (ref "U8") (pin "21") (pinfunction "PA5_21") (pintype "bidirectional"))
    )
    (net (code "92") (name "/PA6") (class "Default")
      (node (ref "U3") (pin "111") (pinfunction "IO_L19P_3_111") (pintype "bidirectional"))
      (node (ref "U8") (pin "22") (pinfunction "PA6_22") (pintype "bidirectional"))
    )
    (net (code "93") (name "/PA7") (class "Default")
      (node (ref "U3") (pin "113") (pinfunction "IO_L19N_3_113") (pintype "bidirectional"))
      (node (ref "U8") (pin "23") (pinfunction "PA7_23") (pintype "bidirectional"))
    )
    (net (code "94") (name "/PA8") (class "Default")
      (node (ref "U3") (pin "114") (pinfunction "IO_L20P_3_114") (pintype "bidirectional"))
      (node (ref "U8") (pin "41") (pinfunction "PA8_41") (pintype "bidirectional"))
    )
    (net (code "95") (name "/PA11") (class "Default")
      (node (ref "U3") (pin "115") (pinfunction "IO_L20N_3_115") (pintype "bidirectional"))
      (node (ref "U8") (pin "44") (pinfunction "PA11_44") (pintype "bidirectional"))
    )
    (net (code "96") (name "/PB50") (class "Default")
      (node (ref "U3") (pin "148") (pinfunction "IO_L20P_2_148") (pintype "bidirectional"))
      (node (ref "U8") (pin "50") (pinfunction "PA15/JTDI_50") (pintype "bidirectional"))
    )
    (net (code "97") (name "/PB55") (class "Default")
      (node (ref "U3") (pin "139") (pinfunction "IO_L24N_2_139") (pintype "bidirectional"))
      (node (ref "U8") (pin "57") (pinfunction "PB5_57") (pintype "bidirectional"))
    )
    (net (code "98") (name "/PB56") (class "Default")
      (node (ref "U3") (pin "140") (pinfunction "IO_L23P_2_140") (pintype "bidirectional"))
      (node (ref "U8") (pin "56") (pinfunction "PB4/JNTRST_56") (pintype "bidirectional"))
    )
    (net (code "99") (name "/PB57") (class "Default")
      (node (ref "U3") (pin "141") (pinfunction "IO_L23N_2/VREF_2_141") (pintype "bidirectional"))
      (node (ref "U8") (pin "55") (pinfunction "PB3/JTDO_55") (pintype "bidirectional"))
    )
    (net (code "100") (name "/PC51") (class "Default")
      (node (ref "U3") (pin "144") (pinfunction "IO_L22N_2_144") (pintype "bidirectional"))
      (node (ref "U8") (pin "53") (pinfunction "PC12_53") (pintype "bidirectional"))
    )
    (net (code "101") (name "/PC52") (class "Default")
      (node (ref "U3") (pin "146") (pinfunction "IO_L21P_2_146") (pintype "bidirectional"))
      (node (ref "U8") (pin "52") (pinfunction "PC11_52") (pintype "bidirectional"))
    )
    (net (code "102") (name "/PC53") (class "Default")
      (node (ref "U3") (pin "147") (pinfunction "IO_L21N_2_147") (pintype "bidirectional"))
      (node (ref "U8") (pin "51") (pinfunction "PC10_51") (pintype "bidirectional"))
    )
    (net (code "103") (name "/PD54") (class "Default")
      (node (ref "U3") (pin "143") (pinfunction "IO_L22P_2_143") (pintype "bidirectional"))
      (node (ref "U8") (pin "54") (pinfunction "PD2_54") (pintype "bidirectional"))
    )
    (net (code "104") (name "/PP20") (class "Default")
      (node (ref "P6") (pin "2") (pinfunction "2_2") (pintype "passive"))
      (node (ref "U3") (pin "20") (pinfunction "IO_L24P_7_20") (pintype "bidirectional"))
    )
    (net (code "105") (name "/PP21") (class "Default")
      (node (ref "P6") (pin "1") (pinfunction "1_1") (pintype "passive"))
      (node (ref "U3") (pin "21") (pinfunction "IO_L24N_7_21") (pintype "bidirectional"))
    )
    (net (code "106") (name "/PP22") (class "Default")
      (node (ref "P6") (pin "4") (pinfunction "4_4") (pintype "passive"))
      (node (ref "U3") (pin "22") (pinfunction "IO_L39P_7_22") (pintype "bidirectional"))
    )
    (net (code "107") (name "/PP24") (class "Default")
      (node (ref "P6") (pin "3") (pinfunction "3_3") (pintype "passive"))
      (node (ref "U3") (pin "24") (pinfunction "IO_L39N_7_24") (pintype "bidirectional"))
    )
    (net (code "108") (name "/PP26") (class "Default")
      (node (ref "P6") (pin "6") (pinfunction "6_6") (pintype "passive"))
      (node (ref "U3") (pin "26") (pinfunction "IO_L40P_7_26") (pintype "bidirectional"))
    )
    (net (code "109") (name "/PP27") (class "Default")
      (node (ref "P6") (pin "5") (pinfunction "5_5") (pintype "passive"))
      (node (ref "U3") (pin "27") (pinfunction "IO_L40N_7/VREF_7_27") (pintype "bidirectional"))
    )
    (net (code "110") (name "/PP28") (class "Default")
      (node (ref "P6") (pin "8") (pinfunction "8_8") (pintype "passive"))
      (node (ref "U3") (pin "28") (pinfunction "IO_L40P_6/VREF_6_28") (pintype "bidirectional"))
    )
    (net (code "111") (name "/PP29") (class "Default")
      (node (ref "P6") (pin "7") (pinfunction "7_7") (pintype "passive"))
      (node (ref "U3") (pin "29") (pinfunction "IO_L40N_6_29") (pintype "bidirectional"))
    )
    (net (code "112") (name "/PP31") (class "Default")
      (node (ref "P6") (pin "10") (pinfunction "10_10") (pintype "passive"))
      (node (ref "U3") (pin "31") (pinfunction "IO_L39P_6_31") (pintype "bidirectional"))
    )
    (net (code "113") (name "/PP33") (class "Default")
      (node (ref "P6") (pin "9") (pinfunction "9_9") (pintype "passive"))
      (node (ref "U3") (pin "33") (pinfunction "IO_L39N_6_33") (pintype "bidirectional"))
    )
    (net (code "114") (name "/PP34") (class "Default")
      (node (ref "P6") (pin "12") (pinfunction "12_12") (pintype "passive"))
      (node (ref "U3") (pin "34") (pinfunction "IO_L24P_6_34") (pintype "bidirectional"))
    )
    (net (code "115") (name "/PP35") (class "Default")
      (node (ref "P6") (pin "11") (pinfunction "11_11") (pintype "passive"))
      (node (ref "U3") (pin "35") (pinfunction "IO_L24N_6/VREF_6_35") (pintype "bidirectional"))
    )
    (net (code "116") (name "/PP36") (class "Default")
      (node (ref "P6") (pin "14") (pinfunction "14_14") (pintype "passive"))
      (node (ref "U3") (pin "36") (pinfunction "IO_L23P_6_36") (pintype "bidirectional"))
    )
    (net (code "117") (name "/PP37") (class "Default")
      (node (ref "P6") (pin "13") (pinfunction "13_13") (pintype "passive"))
      (node (ref "U3") (pin "37") (pinfunction "IO_L23N_6_37") (pintype "bidirectional"))
    )
    (net (code "118") (name "/PP39") (class "Default")
      (node (ref "P6") (pin "16") (pinfunction "16_16") (pintype "passive"))
      (node (ref "U3") (pin "39") (pinfunction "IO_L22P_6_39") (pintype "bidirectional"))
    )
    (net (code "119") (name "/PP40") (class "Default")
      (node (ref "P6") (pin "15") (pinfunction "15_15") (pintype "passive"))
      (node (ref "U3") (pin "40") (pinfunction "IO_L22N_6_40") (pintype "bidirectional"))
    )
    (net (code "120") (name "/PP42") (class "Default")
      (node (ref "P6") (pin "18") (pinfunction "18_18") (pintype "passive"))
      (node (ref "U3") (pin "42") (pinfunction "IO_L21P_6_42") (pintype "bidirectional"))
    )
    (net (code "121") (name "/PP43") (class "Default")
      (node (ref "P6") (pin "17") (pinfunction "17_17") (pintype "passive"))
      (node (ref "U3") (pin "43") (pinfunction "IO_L21N_6_43") (pintype "bidirectional"))
    )
    (net (code "122") (name "/PP44") (class "Default")
      (node (ref "P6") (pin "20") (pinfunction "20_20") (pintype "passive"))
      (node (ref "U3") (pin "44") (pinfunction "IO_L20P_6_44") (pintype "bidirectional"))
    )
    (net (code "123") (name "/PP48") (class "Default")
      (node (ref "P6") (pin "19") (pinfunction "19_19") (pintype "passive"))
      (node (ref "U3") (pin "48") (pinfunction "IO_L19N_6_48") (pintype "bidirectional"))
    )
    (net (code "124") (name "/PP50") (class "Default")
      (node (ref "P6") (pin "22") (pinfunction "22_22") (pintype "passive"))
      (node (ref "U3") (pin "50") (pinfunction "IO/VREF_6_50") (pintype "bidirectional"))
    )
    (net (code "125") (name "/PP51") (class "Default")
      (node (ref "P6") (pin "21") (pinfunction "21_21") (pintype "passive"))
      (node (ref "U3") (pin "51") (pinfunction "IO_L01P_6/VRN_6_51") (pintype "bidirectional"))
    )
    (net (code "126") (name "/PP52") (class "Default")
      (node (ref "P6") (pin "24") (pinfunction "24_24") (pintype "passive"))
      (node (ref "U3") (pin "52") (pinfunction "IO_L01N_6/VRP_6_52") (pintype "bidirectional"))
    )
    (net (code "127") (name "/PP78") (class "Default")
      (node (ref "P6") (pin "23") (pinfunction "23_23") (pintype "passive"))
      (node (ref "U3") (pin "85") (pinfunction "IO/VREF_4_85") (pintype "bidirectional"))
    )
    (net (code "128") (name "/PP80") (class "Default")
      (node (ref "P6") (pin "26") (pinfunction "26_26") (pintype "passive"))
      (node (ref "U3") (pin "81") (pinfunction "IO_L31P_4/DOUT/BUSY_81") (pintype "bidirectional"))
    )
    (net (code "129") (name "/PP81") (class "Default")
      (node (ref "P6") (pin "25") (pinfunction "25_25") (pintype "passive"))
      (node (ref "U3") (pin "80") (pinfunction "IO_L32N_4/GCLK1_80") (pintype "bidirectional"))
    )
    (net (code "130") (name "/PP85") (class "Default")
      (node (ref "P6") (pin "28") (pinfunction "28_28") (pintype "passive"))
      (node (ref "U3") (pin "78") (pinfunction "IO/VREF_5_78") (pintype "bidirectional"))
    )
    (net (code "131") (name "/PP86") (class "Default")
      (node (ref "P7") (pin "2") (pinfunction "2_2") (pintype "passive"))
      (node (ref "U3") (pin "86") (pinfunction "IO_L30P_4/D3_86") (pintype "bidirectional"))
    )
    (net (code "132") (name "/PP87") (class "Default")
      (node (ref "P7") (pin "1") (pinfunction "1_1") (pintype "passive"))
      (node (ref "U3") (pin "87") (pinfunction "IO_L30N_4/D2_87") (pintype "bidirectional"))
    )
    (net (code "133") (name "/PP90") (class "Default")
      (node (ref "P7") (pin "4") (pinfunction "4_4") (pintype "passive"))
      (node (ref "U3") (pin "90") (pinfunction "IO_L27P_4/D1_90") (pintype "bidirectional"))
    )
    (net (code "134") (name "/PP93") (class "Default")
      (node (ref "P7") (pin "3") (pinfunction "3_3") (pintype "passive"))
      (node (ref "U3") (pin "93") (pinfunction "IO_93") (pintype "bidirectional"))
    )
    (net (code "135") (name "/PP94") (class "Default")
      (node (ref "P7") (pin "6") (pinfunction "6_6") (pintype "passive"))
      (node (ref "U3") (pin "94") (pinfunction "IO_L25P_4_94") (pintype "bidirectional"))
    )
    (net (code "136") (name "/PP95") (class "Default")
      (node (ref "P7") (pin "5") (pinfunction "5_5") (pintype "passive"))
      (node (ref "U3") (pin "95") (pinfunction "IO_L25N_4_95") (pintype "bidirectional"))
    )
    (net (code "137") (name "/PP96") (class "Default")
      (node (ref "P7") (pin "8") (pinfunction "8_8") (pintype "passive"))
      (node (ref "U3") (pin "96") (pinfunction "IO/VREF_4_96") (pintype "bidirectional"))
    )
    (net (code "138") (name "/PP97") (class "Default")
      (node (ref "P7") (pin "7") (pinfunction "7_7") (pintype "passive"))
      (node (ref "U3") (pin "97") (pinfunction "IO_97") (pintype "bidirectional"))
    )
    (net (code "139") (name "/PP100") (class "Default")
      (node (ref "P7") (pin "10") (pinfunction "10_10") (pintype "passive"))
      (node (ref "U3") (pin "100") (pinfunction "IO_L01P_4/VRN_4_100") (pintype "bidirectional"))
    )
    (net (code "140") (name "/PP119") (class "Default")
      (node (ref "P7") (pin "9") (pinfunction "9_9") (pintype "passive"))
      (node (ref "U3") (pin "116") (pinfunction "IO_L21P_3_116") (pintype "bidirectional"))
    )
    (net (code "141") (name "/PP128") (class "Default")
      (node (ref "P7") (pin "12") (pinfunction "12_12") (pintype "passive"))
      (node (ref "U3") (pin "117") (pinfunction "IO_L21N_3_117") (pintype "bidirectional"))
    )
    (net (code "142") (name "/PP130") (class "Default")
      (node (ref "P7") (pin "11") (pinfunction "11_11") (pintype "passive"))
      (node (ref "U3") (pin "119") (pinfunction "IO_L22P_3_119") (pintype "bidirectional"))
    )
    (net (code "143") (name "/PP131") (class "Default")
      (node (ref "P7") (pin "14") (pinfunction "14_14") (pintype "passive"))
      (node (ref "U3") (pin "120") (pinfunction "IO_L22N_3_120") (pintype "bidirectional"))
    )
    (net (code "144") (name "/PP132") (class "Default")
      (node (ref "P7") (pin "13") (pinfunction "13_13") (pintype "passive"))
      (node (ref "U3") (pin "122") (pinfunction "IO_L23P_3/VREF_3_122") (pintype "bidirectional"))
    )
    (net (code "145") (name "/PP133") (class "Default")
      (node (ref "P7") (pin "16") (pinfunction "16_16") (pintype "passive"))
      (node (ref "U3") (pin "123") (pinfunction "IO_L23N_3_123") (pintype "bidirectional"))
    )
    (net (code "146") (name "/PP134") (class "Default")
      (node (ref "P7") (pin "15") (pinfunction "15_15") (pintype "passive"))
      (node (ref "U3") (pin "124") (pinfunction "IO_L24P_3_124") (pintype "bidirectional"))
    )
    (net (code "147") (name "/PP137") (class "Default")
      (node (ref "P7") (pin "18") (pinfunction "18_18") (pintype "passive"))
      (node (ref "U3") (pin "125") (pinfunction "IO_L24N_3_125") (pintype "bidirectional"))
    )
    (net (code "148") (name "/PP138") (class "Default")
      (node (ref "P7") (pin "17") (pinfunction "17_17") (pintype "passive"))
      (node (ref "U3") (pin "126") (pinfunction "IO_L39P_3_126") (pintype "bidirectional"))
    )
    (net (code "149") (name "/PP139") (class "Default")
      (node (ref "P7") (pin "20") (pinfunction "20_20") (pintype "passive"))
      (node (ref "U3") (pin "128") (pinfunction "IO_L39N_3_128") (pintype "bidirectional"))
    )
    (net (code "150") (name "/PP140") (class "Default")
      (node (ref "P7") (pin "19") (pinfunction "19_19") (pintype "passive"))
      (node (ref "U3") (pin "130") (pinfunction "IO_L40P_3_130") (pintype "bidirectional"))
    )
    (net (code "151") (name "/PP141") (class "Default")
      (node (ref "P7") (pin "22") (pinfunction "22_22") (pintype "passive"))
      (node (ref "U3") (pin "131") (pinfunction "IO_L40N_3/VREF_3_131") (pintype "bidirectional"))
    )
    (net (code "152") (name "/PP143") (class "Default")
      (node (ref "P7") (pin "21") (pinfunction "21_21") (pintype "passive"))
      (node (ref "U3") (pin "132") (pinfunction "IO_L40P_2/VREF_2_132") (pintype "bidirectional"))
    )
    (net (code "153") (name "/PP144") (class "Default")
      (node (ref "P7") (pin "24") (pinfunction "24_24") (pintype "passive"))
      (node (ref "U3") (pin "133") (pinfunction "IO_L40N_2_133") (pintype "bidirectional"))
    )
    (net (code "154") (name "/PP146") (class "Default")
      (node (ref "P7") (pin "23") (pinfunction "23_23") (pintype "passive"))
      (node (ref "U3") (pin "135") (pinfunction "IO_L39P_2_135") (pintype "bidirectional"))
    )
    (net (code "155") (name "/PP147") (class "Default")
      (node (ref "P7") (pin "26") (pinfunction "26_26") (pintype "passive"))
      (node (ref "U3") (pin "137") (pinfunction "IO_L39N_2_137") (pintype "bidirectional"))
    )
    (net (code "156") (name "/PP148") (class "Default")
      (node (ref "P7") (pin "25") (pinfunction "25_25") (pintype "passive"))
      (node (ref "U3") (pin "138") (pinfunction "IO_L24P_2_138") (pintype "bidirectional"))
    )
    (net (code "157") (name "/RED0") (class "Default")
      (node (ref "R17") (pin "2") (pinfunction "2_2") (pintype "passive"))
      (node (ref "U3") (pin "77") (pinfunction "IO_L32N_5/GCLK3_77") (pintype "bidirectional"))
    )
    (net (code "158") (name "/RED1") (class "Default")
      (node (ref "R16") (pin "2") (pinfunction "2_2") (pintype "passive"))
      (node (ref "U3") (pin "76") (pinfunction "IO_L32P_5/GCLK2_76") (pintype "bidirectional"))
    )
    (net (code "159") (name "/RED2") (class "Default")
      (node (ref "R14") (pin "2") (pinfunction "2_2") (pintype "passive"))
      (node (ref "U3") (pin "74") (pinfunction "IO_L31N_5/D4_74") (pintype "bidirectional"))
    )
    (net (code "160") (name "/RED3") (class "Default")
      (node (ref "R13") (pin "2") (pinfunction "2_2") (pintype "passive"))
      (node (ref "U3") (pin "72") (pinfunction "IO_L31P_5/D5_72") (pintype "bidirectional"))
    )
    (net (code "161") (name "/RS") (class "Default")
      (node (ref "LCD1") (pin "4") (pinfunction "RS_4") (pintype "passive"))
      (node (ref "U8") (pin "39") (pinfunction "PC8_39") (pintype "bidirectional"))
    )
    (net (code "162") (name "/RW") (class "Default")
      (node (ref "LCD1") (pin "5") (pinfunction "RW_5") (pintype "passive"))
      (node (ref "U8") (pin "38") (pinfunction "PC7_38") (pintype "bidirectional"))
    )
    (net (code "163") (name "/RXD0_PA9") (class "Default")
      (node (ref "U1") (pin "1") (pinfunction "TXD_1") (pintype "passive"))
      (node (ref "U8") (pin "42") (pinfunction "PA9_42") (pintype "bidirectional"))
    )
    (net (code "164") (name "/RXD_F2232{slash}MPSSE_TDI") (class "Default")
      (node (ref "U3") (pin "149") (pinfunction "IO_L20N_2_149") (pintype "bidirectional"))
      (node (ref "U9") (pin "39") (pinfunction "BDBUS1_39") (pintype "bidirectional"))
    )
    (net (code "165") (name "/RX_232") (class "Default")
      (node (ref "U14") (pin "12") (pinfunction "R1OUT_12") (pintype "output"))
      (node (ref "U3") (pin "7") (pinfunction "IO_L19P_7_7") (pintype "bidirectional"))
    )
    (net (code "166") (name "/SCL") (class "Default")
      (node (ref "R43") (pin "1") (pinfunction "1_1") (pintype "passive"))
      (node (ref "U13") (pin "6") (pinfunction "SCL_6") (pintype "passive"))
      (node (ref "U8") (pin "58") (pinfunction "PB6_58") (pintype "bidirectional"))
    )
    (net (code "167") (name "/SDA") (class "Default")
      (node (ref "R44") (pin "1") (pinfunction "1_1") (pintype "passive"))
      (node (ref "U13") (pin "5") (pinfunction "SDA_5") (pintype "passive"))
      (node (ref "U8") (pin "59") (pinfunction "PB7_59") (pintype "bidirectional"))
    )
    (net (code "168") (name "/SWCLK") (class "Default")
      (node (ref "P2") (pin "2") (pinfunction "2_2") (pintype "passive"))
      (node (ref "R27") (pin "1") (pinfunction "1_1") (pintype "passive"))
      (node (ref "U8") (pin "49") (pinfunction "PA14/JTCK/SWCLK_49") (pintype "bidirectional"))
    )
    (net (code "169") (name "/SWDIO") (class "Default")
      (node (ref "P2") (pin "1") (pinfunction "1_1") (pintype "passive"))
      (node (ref "R26") (pin "1") (pinfunction "1_1") (pintype "passive"))
      (node (ref "U8") (pin "46") (pinfunction "PA13/JTMS/SWDIO_46") (pintype "bidirectional"))
    )
    (net (code "170") (name "/TCK") (class "Default")
      (node (ref "P5") (pin "1") (pinfunction "1_1") (pintype "passive"))
      (node (ref "R42") (pin "1") (pinfunction "1_1") (pintype "passive"))
      (node (ref "U12") (pin "6") (pinfunction "TCK_6") (pintype "input"))
      (node (ref "U9") (pin "16") (pinfunction "ADBUS0_16") (pintype "bidirectional"))
    )
    (net (code "171") (name "/TDI") (class "Default")
      (node (ref "P5") (pin "9") (pinfunction "9_9") (pintype "passive"))
      (node (ref "U12") (pin "4") (pinfunction "TDI_4") (pintype "input"))
      (node (ref "U9") (pin "17") (pinfunction "ADBUS1_17") (pintype "bidirectional"))
    )
    (net (code "172") (name "/TDO") (class "Default")
      (node (ref "P5") (pin "3") (pinfunction "3_3") (pintype "passive"))
      (node (ref "U3") (pin "158") (pinfunction "TDO_158") (pintype "output"))
      (node (ref "U9") (pin "18") (pinfunction "ADBUS2_18") (pintype "bidirectional"))
    )
    (net (code "173") (name "/TMS") (class "Default")
      (node (ref "P5") (pin "5") (pinfunction "5_5") (pintype "passive"))
      (node (ref "R45") (pin "1") (pinfunction "1_1") (pintype "passive"))
      (node (ref "U12") (pin "5") (pinfunction "TMS_5") (pintype "input"))
      (node (ref "U9") (pin "19") (pinfunction "ADBUS3_19") (pintype "bidirectional"))
    )
    (net (code "174") (name "/TXD0_PA10") (class "Default")
      (node (ref "U1") (pin "5") (pinfunction "RXD_5") (pintype "passive"))
      (node (ref "U8") (pin "43") (pinfunction "PA10_43") (pintype "bidirectional"))
    )
    (net (code "175") (name "/TXD_F2232{slash}MPSSE_TCK") (class "Default")
      (node (ref "U3") (pin "150") (pinfunction "IO_L19P_2_150") (pintype "bidirectional"))
      (node (ref "U9") (pin "38") (pinfunction "BDBUS0_38") (pintype "bidirectional"))
    )
    (net (code "176") (name "/TX_232") (class "Default")
      (node (ref "U14") (pin "11") (pinfunction "T1IN_11") (pintype "input"))
      (node (ref "U3") (pin "9") (pinfunction "IO_L19N_7/VREF_7_9") (pintype "bidirectional"))
    )
    (net (code "177") (name "/UB") (class "Default")
      (node (ref "U2") (pin "40") (pinfunction "~{UB}_40") (pintype "passive"))
      (node (ref "U3") (pin "190") (pinfunction "IO_L30P_0_190") (pintype "bidirectional"))
    )
    (net (code "178") (name "/UTOF") (class "Default")
      (node (ref "U3") (pin "102") (pinfunction "IO/VREF_4_102") (pintype "bidirectional"))
      (node (ref "U8") (pin "62") (pinfunction "PB9_62") (pintype "bidirectional"))
    )
    (net (code "179") (name "/VSYNC") (class "Default")
      (node (ref "R2") (pin "2") (pinfunction "2_2") (pintype "passive"))
      (node (ref "U3") (pin "58") (pinfunction "IO_L01N_5/RDWR_B_58") (pintype "bidirectional"))
    )
    (net (code "180") (name "/WE") (class "Default")
      (node (ref "U2") (pin "17") (pinfunction "~{WE}_17") (pintype "passive"))
      (node (ref "U3") (pin "162") (pinfunction "IO_L01N_1/VRP_1_162") (pintype "bidirectional"))
    )
    (net (code "181") (name "1V2") (class "Default")
      (node (ref "C17") (pin "1") (pinfunction "1_1") (pintype "passive"))
      (node (ref "C18") (pin "2") (pinfunction "2_2") (pintype "passive"))
      (node (ref "C67") (pin "2") (pinfunction "2_2") (pintype "passive"))
      (node (ref "C68") (pin "2") (pinfunction "2_2") (pintype "passive"))
      (node (ref "C69") (pin "2") (pinfunction "2_2") (pintype "passive"))
      (node (ref "C70") (pin "2") (pinfunction "2_2") (pintype "passive"))
      (node (ref "R24") (pin "2") (pinfunction "2_2") (pintype "passive"))
      (node (ref "U3") (pin "174") (pinfunction "VCCINT_174") (pintype "power_in"))
      (node (ref "U3") (pin "192") (pinfunction "VCCINT_192") (pintype "power_in"))
      (node (ref "U3") (pin "70") (pinfunction "VCCINT_70") (pintype "power_in"))
      (node (ref "U3") (pin "88") (pinfunction "VCCINT_88") (pintype "power_in"))
      (node (ref "U6") (pin "2") (pinfunction "OUT_2") (pintype "passive"))
    )
    (net (code "182") (name "1V8") (class "Default")
      (node (ref "C13") (pin "1") (pinfunction "1_1") (pintype "passive"))
      (node (ref "C14") (pin "2") (pinfunction "2_2") (pintype "passive"))
      (node (ref "C21") (pin "2") (pinfunction "2_2") (pintype "passive"))
      (node (ref "C22") (pin "2") (pinfunction "2_2") (pintype "passive"))
      (node (ref "R23") (pin "2") (pinfunction "2_2") (pintype "passive"))
      (node (ref "U4") (pin "2") (pinfunction "OUT_2") (pintype "passive"))
      (node (ref "U9") (pin "12") (pinfunction "VCORE_12") (pintype "power_in"))
      (node (ref "U9") (pin "37") (pinfunction "VCORE_37") (pintype "power_in"))
      (node (ref "U9") (pin "49") (pinfunction "VREGOUT_49") (pintype "power_in"))
      (node (ref "U9") (pin "64") (pinfunction "VCORE_64") (pintype "power_in"))
    )
    (net (code "183") (name "2V5") (class "Default")
      (node (ref "C15") (pin "1") (pinfunction "1_1") (pintype "passive"))
      (node (ref "C16") (pin "2") (pinfunction "2_2") (pintype "passive"))
      (node (ref "C45") (pin "2") (pinfunction "2_2") (pintype "passive"))
      (node (ref "C46") (pin "2") (pinfunction "2_2") (pintype "passive"))
      (node (ref "C47") (pin "2") (pinfunction "2_2") (pintype "passive"))
      (node (ref "C48") (pin "2") (pinfunction "2_2") (pintype "passive"))
      (node (ref "C49") (pin "2") (pinfunction "2_2") (pintype "passive"))
      (node (ref "C59") (pin "2") (pinfunction "2_2") (pintype "passive"))
      (node (ref "C60") (pin "2") (pinfunction "2_2") (pintype "passive"))
      (node (ref "C61") (pin "2") (pinfunction "2_2") (pintype "passive"))
      (node (ref "P7") (pin "28") (pinfunction "28_28") (pintype "passive"))
      (node (ref "R22") (pin "2") (pinfunction "2_2") (pintype "passive"))
      (node (ref "R36") (pin "2") (pinfunction "2_2") (pintype "passive"))
      (node (ref "R37") (pin "2") (pinfunction "2_2") (pintype "passive"))
      (node (ref "R38") (pin "2") (pinfunction "2_2") (pintype "passive"))
      (node (ref "U3") (pin "121") (pinfunction "VCCAUX_121") (pintype "power_in"))
      (node (ref "U3") (pin "142") (pinfunction "VCCAUX_142") (pintype "power_in"))
      (node (ref "U3") (pin "17") (pinfunction "VCCAUX_17") (pintype "power_in"))
      (node (ref "U3") (pin "173") (pinfunction "VCCAUX_173") (pintype "power_in"))
      (node (ref "U3") (pin "193") (pinfunction "VCCAUX_193") (pintype "power_in"))
      (node (ref "U3") (pin "38") (pinfunction "VCCAUX_38") (pintype "power_in"))
      (node (ref "U3") (pin "69") (pinfunction "VCCAUX_69") (pintype "power_in"))
      (node (ref "U3") (pin "89") (pinfunction "VCCAUX_89") (pintype "power_in"))
      (node (ref "U5") (pin "2") (pinfunction "OUT_2") (pintype "passive"))
    )
    (net (code "184") (name "3V3") (class "Default")
      (node (ref "C1") (pin "2") (pinfunction "2_2") (pintype "passive"))
      (node (ref "C10") (pin "2") (pinfunction "2_2") (pintype "passive"))
      (node (ref "C11") (pin "2") (pinfunction "2_2") (pintype "passive"))
      (node (ref "C2") (pin "2") (pinfunction "2_2") (pintype "passive"))
      (node (ref "C27") (pin "1") (pinfunction "1_1") (pintype "passive"))
      (node (ref "C28") (pin "2") (pinfunction "2_2") (pintype "passive"))
      (node (ref "C3") (pin "1") (pinfunction "1_1") (pintype "passive"))
      (node (ref "C33") (pin "2") (pinfunction "2_2") (pintype "passive"))
      (node (ref "C37") (pin "2") (pinfunction "2_2") (pintype "passive"))
      (node (ref "C39") (pin "2") (pinfunction "2_2") (pintype "passive"))
      (node (ref "C4") (pin "1") (pinfunction "1_1") (pintype "passive"))
      (node (ref "C40") (pin "2") (pinfunction "2_2") (pintype "passive"))
      (node (ref "C41") (pin "2") (pinfunction "2_2") (pintype "passive"))
      (node (ref "C42") (pin "2") (pinfunction "2_2") (pintype "passive"))
      (node (ref "C51") (pin "1") (pinfunction "1_1") (pintype "passive"))
      (node (ref "C53") (pin "2") (pinfunction "2_2") (pintype "passive"))
      (node (ref "C54") (pin "2") (pinfunction "2_2") (pintype "passive"))
      (node (ref "C55") (pin "2") (pinfunction "2_2") (pintype "passive"))
      (node (ref "C56") (pin "2") (pinfunction "2_2") (pintype "passive"))
      (node (ref "C57") (pin "2") (pinfunction "2_2") (pintype "passive"))
      (node (ref "C58") (pin "2") (pinfunction "2_2") (pintype "passive"))
      (node (ref "C6") (pin "2") (pinfunction "2_2") (pintype "passive"))
      (node (ref "C62") (pin "2") (pinfunction "2_2") (pintype "passive"))
      (node (ref "C63") (pin "2") (pinfunction "2_2") (pintype "passive"))
      (node (ref "C64") (pin "2") (pinfunction "2_2") (pintype "passive"))
      (node (ref "C65") (pin "2") (pinfunction "2_2") (pintype "passive"))
      (node (ref "C71") (pin "2") (pinfunction "2_2") (pintype "passive"))
      (node (ref "C72") (pin "2") (pinfunction "2_2") (pintype "passive"))
      (node (ref "C73") (pin "2") (pinfunction "2_2") (pintype "passive"))
      (node (ref "C74") (pin "2") (pinfunction "2_2") (pintype "passive"))
      (node (ref "C75") (pin "2") (pinfunction "2_2") (pintype "passive"))
      (node (ref "C76") (pin "2") (pinfunction "2_2") (pintype "passive"))
      (node (ref "C8") (pin "2") (pinfunction "2_2") (pintype "passive"))
      (node (ref "C9") (pin "2") (pinfunction "2_2") (pintype "passive"))
      (node (ref "F1") (pin "1") (pinfunction "1_1") (pintype "passive"))
      (node (ref "F2") (pin "1") (pinfunction "1_1") (pintype "passive"))
      (node (ref "F4") (pin "1") (pinfunction "1_1") (pintype "passive"))
      (node (ref "OSC1") (pin "4") (pinfunction "VCC_4") (pintype "passive"))
      (node (ref "P2") (pin "4") (pinfunction "4_4") (pintype "passive"))
      (node (ref "P3") (pin "17") (pinfunction "17_17") (pintype "passive"))
      (node (ref "P5") (pin "4") (pinfunction "4_4") (pintype "passive"))
      (node (ref "P6") (pin "27") (pinfunction "27_27") (pintype "passive"))
      (node (ref "P7") (pin "27") (pinfunction "27_27") (pintype "passive"))
      (node (ref "R15") (pin "2") (pinfunction "2_2") (pintype "passive"))
      (node (ref "R25") (pin "2") (pinfunction "2_2") (pintype "passive"))
      (node (ref "R26") (pin "2") (pinfunction "2_2") (pintype "passive"))
      (node (ref "R27") (pin "2") (pinfunction "2_2") (pintype "passive"))
      (node (ref "R32") (pin "1") (pinfunction "1_1") (pintype "passive"))
      (node (ref "R43") (pin "2") (pinfunction "2_2") (pintype "passive"))
      (node (ref "R44") (pin "2") (pinfunction "2_2") (pintype "passive"))
      (node (ref "R46") (pin "2") (pinfunction "2_2") (pintype "passive"))
      (node (ref "S1") (pin "10") (pinfunction "B7_10") (pintype "passive"))
      (node (ref "S1") (pin "11") (pinfunction "B6_11") (pintype "passive"))
      (node (ref "S1") (pin "12") (pinfunction "B5_12") (pintype "passive"))
      (node (ref "S1") (pin "13") (pinfunction "B4_13") (pintype "passive"))
      (node (ref "S1") (pin "14") (pinfunction "B3_14") (pintype "passive"))
      (node (ref "S1") (pin "15") (pinfunction "B2_15") (pintype "passive"))
      (node (ref "S1") (pin "16") (pinfunction "B1_16") (pintype "passive"))
      (node (ref "S1") (pin "9") (pinfunction "B8_9") (pintype "passive"))
      (node (ref "S2") (pin "2") (pinfunction "2_2") (pintype "passive"))
      (node (ref "S3") (pin "2") (pinfunction "2_2") (pintype "passive"))
      (node (ref "S4") (pin "2") (pinfunction "2_2") (pintype "passive"))
      (node (ref "S5") (pin "2") (pinfunction "2_2") (pintype "passive"))
      (node (ref "S8") (pin "1") (pinfunction "COMMON_1") (pintype "passive"))
      (node (ref "U12") (pin "18") (pinfunction "VCCINT_18") (pintype "power_in"))
      (node (ref "U12") (pin "19") (pinfunction "VCCO_19") (pintype "power_in"))
      (node (ref "U12") (pin "20") (pinfunction "VCCJ_20") (pintype "power_in"))
      (node (ref "U13") (pin "8") (pinfunction "VCC_8") (pintype "passive"))
      (node (ref "U14") (pin "16") (pinfunction "VCC_16") (pintype "power_in"))
      (node (ref "U2") (pin "11") (pinfunction "VDD_11") (pintype "passive"))
      (node (ref "U2") (pin "33") (pinfunction "VDD_33") (pintype "passive"))
      (node (ref "U3") (pin "110") (pinfunction "VCCO_3_110") (pintype "power_in"))
      (node (ref "U3") (pin "127") (pinfunction "VCCO_3_127") (pintype "power_in"))
      (node (ref "U3") (pin "136") (pinfunction "VCCO_2_136") (pintype "power_in"))
      (node (ref "U3") (pin "153") (pinfunction "VCCO_2_153") (pintype "power_in"))
      (node (ref "U3") (pin "164") (pinfunction "VCCO_1_164") (pintype "power_in"))
      (node (ref "U3") (pin "177") (pinfunction "VCCO_1_177") (pintype "power_in"))
      (node (ref "U3") (pin "188") (pinfunction "VCCO_0_188") (pintype "power_in"))
      (node (ref "U3") (pin "201") (pinfunction "VCCO_0_201") (pintype "power_in"))
      (node (ref "U3") (pin "23") (pinfunction "VCCO_7_23") (pintype "power_in"))
      (node (ref "U3") (pin "32") (pinfunction "VCCO_6_32") (pintype "power_in"))
      (node (ref "U3") (pin "49") (pinfunction "VCCO_6_49") (pintype "power_in"))
      (node (ref "U3") (pin "6") (pinfunction "VCCO_7_6") (pintype "power_in"))
      (node (ref "U3") (pin "60") (pinfunction "VCCO_5_60") (pintype "power_in"))
      (node (ref "U3") (pin "73") (pinfunction "VCCO_5_73") (pintype "power_in"))
      (node (ref "U3") (pin "84") (pinfunction "VCCO_4_84") (pintype "power_in"))
      (node (ref "U3") (pin "98") (pinfunction "VCCO_4_98") (pintype "power_in"))
      (node (ref "U7") (pin "2") (pinfunction "OUT_2") (pintype "passive"))
      (node (ref "U8") (pin "1") (pinfunction "VBAT_1") (pintype "power_in"))
      (node (ref "U8") (pin "19") (pinfunction "VDD_4_19") (pintype "power_in"))
      (node (ref "U8") (pin "32") (pinfunction "VDD_1_32") (pintype "power_in"))
      (node (ref "U8") (pin "48") (pinfunction "VDD_2_48") (pintype "power_in"))
      (node (ref "U8") (pin "64") (pinfunction "VDD_3_64") (pintype "power_in"))
      (node (ref "U9") (pin "20") (pinfunction "VCCIO_20") (pintype "power_in"))
      (node (ref "U9") (pin "31") (pinfunction "VCCIO_31") (pintype "power_in"))
      (node (ref "U9") (pin "42") (pinfunction "VCCIO_42") (pintype "power_in"))
      (node (ref "U9") (pin "50") (pinfunction "VREGIN_50") (pintype "power_in"))
      (node (ref "U9") (pin "56") (pinfunction "VCCIO_56") (pintype "power_in"))
    )
    (net (code "185") (name "3V3A") (class "Default")
      (node (ref "C38") (pin "2") (pinfunction "2_2") (pintype "passive"))
      (node (ref "F4") (pin "2") (pinfunction "2_2") (pintype "passive"))
      (node (ref "U8") (pin "13") (pinfunction "VDDA_13") (pintype "power_in"))
    )
    (net (code "186") (name "5V0") (class "Default")
      (node (ref "C12") (pin "2") (pinfunction "2_2") (pintype "passive"))
      (node (ref "C19") (pin "2") (pinfunction "2_2") (pintype "passive"))
      (node (ref "C20") (pin "2") (pinfunction "2_2") (pintype "passive"))
      (node (ref "C29") (pin "2") (pinfunction "2_2") (pintype "passive"))
      (node (ref "C31") (pin "2") (pinfunction "2_2") (pintype "passive"))
      (node (ref "C7") (pin "2") (pinfunction "2_2") (pintype "passive"))
      (node (ref "F3") (pin "2") (pinfunction "2_2") (pintype "passive"))
      (node (ref "L1") (pin "2") (pinfunction "2_2") (pintype "passive"))
      (node (ref "LCD1") (pin "15") (pinfunction "A_15") (pintype "passive"))
      (node (ref "LCD1") (pin "2") (pinfunction "VCC_2") (pintype "passive"))
      (node (ref "P6") (pin "29") (pinfunction "29_29") (pintype "passive"))
      (node (ref "P7") (pin "29") (pinfunction "29_29") (pintype "passive"))
      (node (ref "R30") (pin "2") (pinfunction "BOT_2") (pintype "passive"))
      (node (ref "R33") (pin "2") (pinfunction "2_2") (pintype "passive"))
      (node (ref "R39") (pin "1") (pinfunction "1_1") (pintype "passive"))
      (node (ref "R7") (pin "2") (pinfunction "2_2") (pintype "passive"))
      (node (ref "R8") (pin "2") (pinfunction "2_2") (pintype "passive"))
      (node (ref "U1") (pin "20") (pinfunction "VCC_20") (pintype "passive"))
      (node (ref "U1") (pin "4") (pinfunction "VCCIO_4") (pintype "passive"))
      (node (ref "U10") (pin "4") (pinfunction "FB_4") (pintype "input"))
      (node (ref "U11") (pin "8") (pinfunction "VCC_8") (pintype "power_in"))
      (node (ref "U4") (pin "3") (pinfunction "IN_3") (pintype "passive"))
      (node (ref "U5") (pin "3") (pinfunction "IN_3") (pintype "passive"))
      (node (ref "U6") (pin "3") (pinfunction "IN_3") (pintype "passive"))
      (node (ref "U7") (pin "3") (pinfunction "IN_3") (pintype "passive"))
    )
    (net (code "187") (name "GND") (class "Default")
      (node (ref "*") (pin "9") (pinfunction "9_9") (pintype "passive"))
      (node (ref "C1") (pin "1") (pinfunction "1_1") (pintype "passive"))
      (node (ref "C12") (pin "1") (pinfunction "1_1") (pintype "passive"))
      (node (ref "C13") (pin "2") (pinfunction "2_2") (pintype "passive"))
      (node (ref "C14") (pin "1") (pinfunction "1_1") (pintype "passive"))
      (node (ref "C15") (pin "2") (pinfunction "2_2") (pintype "passive"))
      (node (ref "C16") (pin "1") (pinfunction "1_1") (pintype "passive"))
      (node (ref "C17") (pin "2") (pinfunction "2_2") (pintype "passive"))
      (node (ref "C18") (pin "1") (pinfunction "1_1") (pintype "passive"))
      (node (ref "C19") (pin "1") (pinfunction "1_1") (pintype "passive"))
      (node (ref "C2") (pin "1") (pinfunction "1_1") (pintype "passive"))
      (node (ref "C20") (pin "1") (pinfunction "1_1") (pintype "passive"))
      (node (ref "C21") (pin "1") (pinfunction "1_1") (pintype "passive"))
      (node (ref "C22") (pin "1") (pinfunction "1_1") (pintype "passive"))
      (node (ref "C23") (pin "1") (pinfunction "1_1") (pintype "passive"))
      (node (ref "C24") (pin "1") (pinfunction "1_1") (pintype "passive"))
      (node (ref "C25") (pin "1") (pinfunction "1_1") (pintype "passive"))
      (node (ref "C26") (pin "1") (pinfunction "1_1") (pintype "passive"))
      (node (ref "C27") (pin "2") (pinfunction "2_2") (pintype "passive"))
      (node (ref "C28") (pin "1") (pinfunction "1_1") (pintype "passive"))
      (node (ref "C29") (pin "1") (pinfunction "1_1") (pintype "passive"))
      (node (ref "C3") (pin "2") (pinfunction "2_2") (pintype "passive"))
      (node (ref "C30") (pin "1") (pinfunction "1_1") (pintype "passive"))
      (node (ref "C31") (pin "1") (pinfunction "1_1") (pintype "passive"))
      (node (ref "C32") (pin "1") (pinfunction "1_1") (pintype "passive"))
      (node (ref "C33") (pin "1") (pinfunction "1_1") (pintype "passive"))
      (node (ref "C34") (pin "1") (pinfunction "1_1") (pintype "passive"))
      (node (ref "C35") (pin "1") (pinfunction "1_1") (pintype "passive"))
      (node (ref "C36") (pin "2") (pinfunction "2_2") (pintype "passive"))
      (node (ref "C37") (pin "1") (pinfunction "1_1") (pintype "passive"))
      (node (ref "C39") (pin "1") (pinfunction "1_1") (pintype "passive"))
      (node (ref "C4") (pin "2") (pinfunction "2_2") (pintype "passive"))
      (node (ref "C40") (pin "1") (pinfunction "1_1") (pintype "passive"))
      (node (ref "C41") (pin "1") (pinfunction "1_1") (pintype "passive"))
      (node (ref "C42") (pin "1") (pinfunction "1_1") (pintype "passive"))
      (node (ref "C43") (pin "1") (pinfunction "1_1") (pintype "passive"))
      (node (ref "C45") (pin "1") (pinfunction "1_1") (pintype "passive"))
      (node (ref "C46") (pin "1") (pinfunction "1_1") (pintype "passive"))
      (node (ref "C47") (pin "1") (pinfunction "1_1") (pintype "passive"))
      (node (ref "C48") (pin "1") (pinfunction "1_1") (pintype "passive"))
      (node (ref "C49") (pin "1") (pinfunction "1_1") (pintype "passive"))
      (node (ref "C5") (pin "1") (pinfunction "1_1") (pintype "passive"))
      (node (ref "C50") (pin "2") (pinfunction "2_2") (pintype "passive"))
      (node (ref "C51") (pin "2") (pinfunction "2_2") (pintype "passive"))
      (node (ref "C53") (pin "1") (pinfunction "1_1") (pintype "passive"))
      (node (ref "C54") (pin "1") (pinfunction "1_1") (pintype "passive"))
      (node (ref "C55") (pin "1") (pinfunction "1_1") (pintype "passive"))
      (node (ref "C56") (pin "1") (pinfunction "1_1") (pintype "passive"))
      (node (ref "C57") (pin "1") (pinfunction "1_1") (pintype "passive"))
      (node (ref "C58") (pin "1") (pinfunction "1_1") (pintype "passive"))
      (node (ref "C59") (pin "1") (pinfunction "1_1") (pintype "passive"))
      (node (ref "C6") (pin "1") (pinfunction "1_1") (pintype "passive"))
      (node (ref "C60") (pin "1") (pinfunction "1_1") (pintype "passive"))
      (node (ref "C61") (pin "1") (pinfunction "1_1") (pintype "passive"))
      (node (ref "C62") (pin "1") (pinfunction "1_1") (pintype "passive"))
      (node (ref "C63") (pin "1") (pinfunction "1_1") (pintype "passive"))
      (node (ref "C64") (pin "1") (pinfunction "1_1") (pintype "passive"))
      (node (ref "C65") (pin "1") (pinfunction "1_1") (pintype "passive"))
      (node (ref "C66") (pin "1") (pinfunction "1_1") (pintype "passive"))
      (node (ref "C67") (pin "1") (pinfunction "1_1") (pintype "passive"))
      (node (ref "C68") (pin "1") (pinfunction "1_1") (pintype "passive"))
      (node (ref "C69") (pin "1") (pinfunction "1_1") (pintype "passive"))
      (node (ref "C7") (pin "1") (pinfunction "1_1") (pintype "passive"))
      (node (ref "C70") (pin "1") (pinfunction "1_1") (pintype "passive"))
      (node (ref "C71") (pin "1") (pinfunction "1_1") (pintype "passive"))
      (node (ref "C72") (pin "1") (pinfunction "1_1") (pintype "passive"))
      (node (ref "C73") (pin "1") (pinfunction "1_1") (pintype "passive"))
      (node (ref "C74") (pin "1") (pinfunction "1_1") (pintype "passive"))
      (node (ref "C75") (pin "1") (pinfunction "1_1") (pintype "passive"))
      (node (ref "C76") (pin "1") (pinfunction "1_1") (pintype "passive"))
      (node (ref "D3") (pin "2") (pinfunction "K_2") (pintype "passive"))
      (node (ref "D4") (pin "2") (pinfunction "K_2") (pintype "passive"))
      (node (ref "D6") (pin "2") (pinfunction "K_2") (pintype "passive"))
      (node (ref "D7") (pin "2") (pinfunction "K_2") (pintype "passive"))
      (node (ref "D8") (pin "3") (pinfunction "A_3") (pintype "passive"))
      (node (ref "F5") (pin "1") (pinfunction "1_1") (pintype "passive"))
      (node (ref "J2") (pin "5") (pinfunction "5_5") (pintype "passive"))
      (node (ref "LCD1") (pin "1") (pinfunction "GND_1") (pintype "passive"))
      (node (ref "LCD1") (pin "16") (pinfunction "K_16") (pintype "passive"))
      (node (ref "OSC1") (pin "2") (pinfunction "GND_2") (pintype "passive"))
      (node (ref "P2") (pin "5") (pinfunction "5_5") (pintype "passive"))
      (node (ref "P3") (pin "18") (pinfunction "18_18") (pintype "passive"))
      (node (ref "P4") (pin "1") (pinfunction "1_1") (pintype "passive"))
      (node (ref "P5") (pin "10") (pinfunction "10_10") (pintype "passive"))
      (node (ref "P5") (pin "2") (pinfunction "2_2") (pintype "passive"))
      (node (ref "P6") (pin "30") (pinfunction "30_30") (pintype "passive"))
      (node (ref "P7") (pin "30") (pinfunction "30_30") (pintype "passive"))
      (node (ref "R18") (pin "1") (pinfunction "1_1") (pintype "passive"))
      (node (ref "R19") (pin "1") (pinfunction "1_1") (pintype "passive"))
      (node (ref "R20") (pin "1") (pinfunction "1_1") (pintype "passive"))
      (node (ref "R21") (pin "1") (pinfunction "1_1") (pintype "passive"))
      (node (ref "R23") (pin "1") (pinfunction "1_1") (pintype "passive"))
      (node (ref "R24") (pin "1") (pinfunction "1_1") (pintype "passive"))
      (node (ref "R28") (pin "1") (pinfunction "1_1") (pintype "passive"))
      (node (ref "R30") (pin "1") (pinfunction "TOP_1") (pintype "passive"))
      (node (ref "R34") (pin "1") (pinfunction "1_1") (pintype "passive"))
      (node (ref "R47") (pin "1") (pinfunction "1_1") (pintype "passive"))
      (node (ref "S7") (pin "1") (pinfunction "1_1") (pintype "passive"))
      (node (ref "S9") (pin "1") (pinfunction "1_1") (pintype "passive"))
      (node (ref "U1") (pin "18") (pinfunction "GND_18") (pintype "passive"))
      (node (ref "U1") (pin "21") (pinfunction "GND_21") (pintype "passive"))
      (node (ref "U1") (pin "25") (pinfunction "AGND_25") (pintype "passive"))
      (node (ref "U1") (pin "26") (pinfunction "TEST_26") (pintype "passive"))
      (node (ref "U1") (pin "7") (pinfunction "GND_7") (pintype "passive"))
      (node (ref "U10") (pin "3") (pinfunction "GND_3") (pintype "power_in"))
      (node (ref "U10") (pin "5") (pinfunction "~{ON}/OFF_5") (pintype "input"))
      (node (ref "U11") (pin "5") (pinfunction "VSS_5") (pintype "power_in"))
      (node (ref "U12") (pin "11") (pinfunction "GND_11") (pintype "power_in"))
      (node (ref "U13") (pin "1") (pinfunction "A0_1") (pintype "passive"))
      (node (ref "U13") (pin "2") (pinfunction "A1_2") (pintype "passive"))
      (node (ref "U13") (pin "3") (pinfunction "NC_3") (pintype "passive"))
      (node (ref "U13") (pin "4") (pinfunction "GND_4") (pintype "passive"))
      (node (ref "U13") (pin "7") (pinfunction "WP_7") (pintype "passive"))
      (node (ref "U14") (pin "15") (pinfunction "GND_15") (pintype "power_in"))
      (node (ref "U2") (pin "12") (pinfunction "GND_12") (pintype "passive"))
      (node (ref "U2") (pin "34") (pinfunction "GND_34") (pintype "passive"))
      (node (ref "U3") (pin "1") (pinfunction "GND_1") (pintype "power_in"))
      (node (ref "U3") (pin "105") (pinfunction "GND_105") (pintype "power_in"))
      (node (ref "U3") (pin "112") (pinfunction "GND_112") (pintype "power_in"))
      (node (ref "U3") (pin "118") (pinfunction "GND_118") (pintype "power_in"))
      (node (ref "U3") (pin "129") (pinfunction "GND_129") (pintype "power_in"))
      (node (ref "U3") (pin "134") (pinfunction "GND_134") (pintype "power_in"))
      (node (ref "U3") (pin "14") (pinfunction "GND_14") (pintype "power_in"))
      (node (ref "U3") (pin "145") (pinfunction "GND_145") (pintype "power_in"))
      (node (ref "U3") (pin "151") (pinfunction "GND_151") (pintype "power_in"))
      (node (ref "U3") (pin "157") (pinfunction "GND_157") (pintype "power_in"))
      (node (ref "U3") (pin "163") (pinfunction "GND_163") (pintype "power_in"))
      (node (ref "U3") (pin "170") (pinfunction "GND_170") (pintype "power_in"))
      (node (ref "U3") (pin "179") (pinfunction "GND_179") (pintype "power_in"))
      (node (ref "U3") (pin "186") (pinfunction "GND_186") (pintype "power_in"))
      (node (ref "U3") (pin "195") (pinfunction "GND_195") (pintype "power_in"))
      (node (ref "U3") (pin "202") (pinfunction "GND_202") (pintype "power_in"))
      (node (ref "U3") (pin "206") (pinfunction "HSWAP_EN_206") (pintype "input"))
      (node (ref "U3") (pin "25") (pinfunction "GND_25") (pintype "power_in"))
      (node (ref "U3") (pin "30") (pinfunction "GND_30") (pintype "power_in"))
      (node (ref "U3") (pin "41") (pinfunction "GND_41") (pintype "power_in"))
      (node (ref "U3") (pin "47") (pinfunction "GND_47") (pintype "power_in"))
      (node (ref "U3") (pin "53") (pinfunction "GND_53") (pintype "power_in"))
      (node (ref "U3") (pin "54") (pinfunction "M1_54") (pintype "input"))
      (node (ref "U3") (pin "55") (pinfunction "M0_55") (pintype "input"))
      (node (ref "U3") (pin "56") (pinfunction "M2_56") (pintype "input"))
      (node (ref "U3") (pin "59") (pinfunction "GND_59") (pintype "power_in"))
      (node (ref "U3") (pin "66") (pinfunction "GND_66") (pintype "power_in"))
      (node (ref "U3") (pin "75") (pinfunction "GND_75") (pintype "power_in"))
      (node (ref "U3") (pin "8") (pinfunction "GND_8") (pintype "power_in"))
      (node (ref "U3") (pin "82") (pinfunction "GND_82") (pintype "power_in"))
      (node (ref "U3") (pin "91") (pinfunction "GND_91") (pintype "power_in"))
      (node (ref "U3") (pin "99") (pinfunction "GND_99") (pintype "power_in"))
      (node (ref "U4") (pin "1") (pinfunction "GND_1") (pintype "passive"))
      (node (ref "U5") (pin "1") (pinfunction "GND_1") (pintype "passive"))
      (node (ref "U6") (pin "1") (pinfunction "GND_1") (pintype "passive"))
      (node (ref "U7") (pin "1") (pinfunction "GND_1") (pintype "passive"))
      (node (ref "U8") (pin "12") (pinfunction "VSSA_12") (pintype "power_in"))
      (node (ref "U8") (pin "18") (pinfunction "VSS_4_18") (pintype "power_in"))
      (node (ref "U8") (pin "31") (pinfunction "VSS_1_31") (pintype "power_in"))
      (node (ref "U8") (pin "47") (pinfunction "VSS_2_47") (pintype "power_in"))
      (node (ref "U8") (pin "63") (pinfunction "VSS_3_63") (pintype "power_in"))
      (node (ref "U9") (pin "1") (pinfunction "GND_1") (pintype "power_in"))
      (node (ref "U9") (pin "10") (pinfunction "AGND_10") (pintype "power_in"))
      (node (ref "U9") (pin "11") (pinfunction "GND_11") (pintype "power_in"))
      (node (ref "U9") (pin "13") (pinfunction "TEST_13") (pintype "input"))
      (node (ref "U9") (pin "15") (pinfunction "GND_15") (pintype "power_in"))
      (node (ref "U9") (pin "25") (pinfunction "GND_25") (pintype "power_in"))
      (node (ref "U9") (pin "35") (pinfunction "GND_35") (pintype "power_in"))
      (node (ref "U9") (pin "47") (pinfunction "GND_47") (pintype "power_in"))
      (node (ref "U9") (pin "5") (pinfunction "GND_5") (pintype "power_in"))
      (node (ref "U9") (pin "51") (pinfunction "GND_51") (pintype "power_in"))
      (node (ref "USB1") (pin "5") (pinfunction "GND_5") (pintype "passive"))
      (node (ref "USB2") (pin "5") (pinfunction "GND_5") (pintype "passive"))
      (node (ref "VGA1") (pin "10") (pinfunction "10_10") (pintype "passive"))
      (node (ref "VGA1") (pin "11") (pinfunction "11_11") (pintype "passive"))
      (node (ref "VGA1") (pin "5") (pinfunction "5_5") (pintype "passive"))
      (node (ref "VGA1") (pin "6") (pinfunction "6_6") (pintype "passive"))
      (node (ref "VGA1") (pin "7") (pinfunction "7_7") (pintype "passive"))
      (node (ref "VGA1") (pin "8") (pinfunction "8_8") (pintype "passive"))
    )
    (net (code "188") (name "GNDA") (class "Default")
      (node (ref "C38") (pin "1") (pinfunction "1_1") (pintype "passive"))
      (node (ref "F5") (pin "2") (pinfunction "2_2") (pintype "passive"))
    )
    (net (code "189") (name "Net-(D1-A)") (class "Default")
      (node (ref "D1") (pin "1") (pinfunction "A_1") (pintype "passive"))
      (node (ref "R7") (pin "1") (pinfunction "1_1") (pintype "passive"))
    )
    (net (code "190") (name "Net-(D1-K)") (class "Default")
      (node (ref "D1") (pin "2") (pinfunction "K_2") (pintype "passive"))
      (node (ref "U1") (pin "23") (pinfunction "CBUS0_23") (pintype "passive"))
    )
    (net (code "191") (name "Net-(D2-A)") (class "Default")
      (node (ref "D2") (pin "1") (pinfunction "A_1") (pintype "passive"))
      (node (ref "R8") (pin "1") (pinfunction "1_1") (pintype "passive"))
    )
    (net (code "192") (name "Net-(D2-K)") (class "Default")
      (node (ref "D2") (pin "2") (pinfunction "K_2") (pintype "passive"))
      (node (ref "U1") (pin "22") (pinfunction "CBUS1_22") (pintype "passive"))
    )
    (net (code "193") (name "Net-(D3-A)") (class "Default")
      (node (ref "D3") (pin "1") (pinfunction "A_1") (pintype "passive"))
      (node (ref "R22") (pin "1") (pinfunction "1_1") (pintype "passive"))
    )
    (net (code "194") (name "Net-(D4-A)") (class "Default")
      (node (ref "D4") (pin "1") (pinfunction "A_1") (pintype "passive"))
      (node (ref "R25") (pin "1") (pinfunction "1_1") (pintype "passive"))
    )
    (net (code "195") (name "Net-(D5-A)") (class "Default")
      (node (ref "D5") (pin "1") (pinfunction "A_1") (pintype "passive"))
      (node (ref "S6") (pin "2") (pinfunction "NO_2") (pintype "passive"))
    )
    (net (code "196") (name "Net-(D5-K)") (class "Default")
      (node (ref "C30") (pin "2") (pinfunction "2_2") (pintype "passive"))
      (node (ref "D5") (pin "2") (pinfunction "K_2") (pintype "passive"))
      (node (ref "U10") (pin "1") (pinfunction "VIN_1") (pintype "power_in"))
    )
    (net (code "197") (name "Net-(D6-A)") (class "Default")
      (node (ref "D6") (pin "1") (pinfunction "A_1") (pintype "passive"))
      (node (ref "R33") (pin "1") (pinfunction "1_1") (pintype "passive"))
    )
    (net (code "198") (name "Net-(D7-A)") (class "Default")
      (node (ref "D7") (pin "1") (pinfunction "A_1") (pintype "passive"))
      (node (ref "R35") (pin "2") (pinfunction "2_2") (pintype "passive"))
    )
    (net (code "199") (name "Net-(D8-K)") (class "Default")
      (node (ref "D8") (pin "1") (pinfunction "K_1") (pintype "passive"))
      (node (ref "L1") (pin "1") (pinfunction "1_1") (pintype "passive"))
      (node (ref "U10") (pin "2") (pinfunction "OUT_2") (pintype "power_in"))
    )
    (net (code "200") (name "Net-(LCD1-VO)") (class "Default")
      (node (ref "LCD1") (pin "3") (pinfunction "VO_3") (pintype "passive"))
      (node (ref "R30") (pin "3") (pinfunction "TAP_3") (pintype "passive"))
    )
    (net (code "201") (name "Net-(OSC1-E{slash}D)") (class "Default")
      (node (ref "OSC1") (pin "1") (pinfunction "E/D_1") (pintype "passive"))
      (node (ref "R15") (pin "1") (pinfunction "1_1") (pintype "passive"))
    )
    (net (code "202") (name "Net-(R1-Pad1)") (class "Default")
      (node (ref "R1") (pin "1") (pinfunction "1_1") (pintype "passive"))
      (node (ref "VGA1") (pin "13") (pinfunction "13_13") (pintype "passive"))
    )
    (net (code "203") (name "Net-(R2-Pad1)") (class "Default")
      (node (ref "R2") (pin "1") (pinfunction "1_1") (pintype "passive"))
      (node (ref "VGA1") (pin "14") (pinfunction "14_14") (pintype "passive"))
    )
    (net (code "204") (name "Net-(R3-Pad1)") (class "Default")
      (node (ref "R3") (pin "1") (pinfunction "1_1") (pintype "passive"))
      (node (ref "R4") (pin "1") (pinfunction "1_1") (pintype "passive"))
      (node (ref "R5") (pin "1") (pinfunction "1_1") (pintype "passive"))
      (node (ref "R6") (pin "1") (pinfunction "1_1") (pintype "passive"))
      (node (ref "VGA1") (pin "3") (pinfunction "3_3") (pintype "passive"))
    )
    (net (code "205") (name "Net-(R10-Pad1)") (class "Default")
      (node (ref "R10") (pin "1") (pinfunction "1_1") (pintype "passive"))
      (node (ref "R11") (pin "1") (pinfunction "1_1") (pintype "passive"))
      (node (ref "R12") (pin "1") (pinfunction "1_1") (pintype "passive"))
      (node (ref "R9") (pin "1") (pinfunction "1_1") (pintype "passive"))
      (node (ref "VGA1") (pin "2") (pinfunction "2_2") (pintype "passive"))
    )
    (net (code "206") (name "Net-(R13-Pad1)") (class "Default")
      (node (ref "R13") (pin "1") (pinfunction "1_1") (pintype "passive"))
      (node (ref "R14") (pin "1") (pinfunction "1_1") (pintype "passive"))
      (node (ref "R16") (pin "1") (pinfunction "1_1") (pintype "passive"))
      (node (ref "R17") (pin "1") (pinfunction "1_1") (pintype "passive"))
      (node (ref "VGA1") (pin "1") (pinfunction "1_1") (pintype "passive"))
    )
    (net (code "207") (name "Net-(S6-COMMON)") (class "Default")
      (node (ref "P4") (pin "2") (pinfunction "2_2") (pintype "passive"))
      (node (ref "S6") (pin "1") (pinfunction "COMMON_1") (pintype "passive"))
    )
    (net (code "208") (name "Net-(U1-3V3OUT)") (class "Default")
      (node (ref "C5") (pin "2") (pinfunction "2_2") (pintype "passive"))
      (node (ref "U1") (pin "17") (pinfunction "3V3OUT_17") (pintype "passive"))
    )
    (net (code "209") (name "Net-(U1-USBDM)") (class "Default")
      (node (ref "U1") (pin "16") (pinfunction "USBDM_16") (pintype "passive"))
      (node (ref "USB1") (pin "2") (pinfunction "D-_2") (pintype "passive"))
    )
    (net (code "210") (name "Net-(U1-USBDP)") (class "Default")
      (node (ref "U1") (pin "15") (pinfunction "USBDP_15") (pintype "passive"))
      (node (ref "USB1") (pin "3") (pinfunction "D+_3") (pintype "passive"))
    )
    (net (code "211") (name "Net-(U3I-TCK)") (class "Default")
      (node (ref "R42") (pin "2") (pinfunction "2_2") (pintype "passive"))
      (node (ref "U3") (pin "159") (pinfunction "TCK_159") (pintype "input"))
    )
    (net (code "212") (name "Net-(U3I-TDI)") (class "Default")
      (node (ref "R41") (pin "2") (pinfunction "2_2") (pintype "passive"))
      (node (ref "U3") (pin "208") (pinfunction "TDI_208") (pintype "input"))
    )
    (net (code "213") (name "Net-(U3I-TMS)") (class "Default")
      (node (ref "R45") (pin "2") (pinfunction "2_2") (pintype "passive"))
      (node (ref "U3") (pin "160") (pinfunction "TMS_160") (pintype "input"))
    )
    (net (code "214") (name "Net-(U9-DM)") (class "Default")
      (node (ref "R29") (pin "2") (pinfunction "2_2") (pintype "passive"))
      (node (ref "U9") (pin "7") (pinfunction "DM_7") (pintype "input"))
    )
    (net (code "215") (name "Net-(U9-DP)") (class "Default")
      (node (ref "R31") (pin "2") (pinfunction "2_2") (pintype "passive"))
      (node (ref "U9") (pin "8") (pinfunction "DP_8") (pintype "input"))
    )
    (net (code "216") (name "Net-(U9-OSCI)") (class "Default")
      (node (ref "C35") (pin "2") (pinfunction "2_2") (pintype "passive"))
      (node (ref "U9") (pin "2") (pinfunction "OSCI_2") (pintype "input"))
      (node (ref "Y2") (pin "1") (pinfunction "OSC1_1") (pintype "passive"))
    )
    (net (code "217") (name "Net-(U9-OSCO)") (class "Default")
      (node (ref "C36") (pin "1") (pinfunction "1_1") (pintype "passive"))
      (node (ref "U9") (pin "3") (pinfunction "OSCO_3") (pintype "output"))
      (node (ref "Y2") (pin "2") (pinfunction "OSC2_2") (pintype "passive"))
    )
    (net (code "218") (name "Net-(U9-REF)") (class "Default")
      (node (ref "R34") (pin "2") (pinfunction "2_2") (pintype "passive"))
      (node (ref "U9") (pin "6") (pinfunction "REF_6") (pintype "input"))
    )
    (net (code "219") (name "Net-(U9-RESET#)") (class "Default")
      (node (ref "R32") (pin "2") (pinfunction "2_2") (pintype "passive"))
      (node (ref "U9") (pin "14") (pinfunction "RESET#_14") (pintype "input"))
    )
    (net (code "220") (name "Net-(U9-VPHY)") (class "Default")
      (node (ref "C24") (pin "2") (pinfunction "2_2") (pintype "passive"))
      (node (ref "C26") (pin "2") (pinfunction "2_2") (pintype "passive"))
      (node (ref "F2") (pin "2") (pinfunction "2_2") (pintype "passive"))
      (node (ref "U9") (pin "4") (pinfunction "VPHY_4") (pintype "power_in"))
    )
    (net (code "221") (name "Net-(U9-VPLL)") (class "Default")
      (node (ref "C23") (pin "2") (pinfunction "2_2") (pintype "passive"))
      (node (ref "C25") (pin "2") (pinfunction "2_2") (pintype "passive"))
      (node (ref "F1") (pin "2") (pinfunction "2_2") (pintype "passive"))
      (node (ref "U9") (pin "9") (pinfunction "VPLL_9") (pintype "power_in"))
    )
    (net (code "222") (name "Net-(U11-CLK)") (class "Default")
      (node (ref "U11") (pin "2") (pinfunction "CLK_2") (pintype "input"))
      (node (ref "U9") (pin "62") (pinfunction "EECLK_62") (pintype "output"))
    )
    (net (code "223") (name "Net-(U11-CS)") (class "Default")
      (node (ref "U11") (pin "1") (pinfunction "CS_1") (pintype "input"))
      (node (ref "U9") (pin "63") (pinfunction "EECS_63") (pintype "bidirectional"))
    )
    (net (code "224") (name "Net-(U11-DI)") (class "Default")
      (node (ref "R40") (pin "2") (pinfunction "2_2") (pintype "passive"))
      (node (ref "U11") (pin "3") (pinfunction "DI_3") (pintype "input"))
      (node (ref "U9") (pin "61") (pinfunction "EEDATA_61") (pintype "bidirectional"))
    )
    (net (code "225") (name "Net-(U11-DO)") (class "Default")
      (node (ref "R39") (pin "2") (pinfunction "2_2") (pintype "passive"))
      (node (ref "R40") (pin "1") (pinfunction "1_1") (pintype "passive"))
      (node (ref "U11") (pin "4") (pinfunction "DO_4") (pintype "tri_state"))
    )
    (net (code "226") (name "Net-(U12-CLK)") (class "Default")
      (node (ref "U12") (pin "3") (pinfunction "CLK_3") (pintype "input"))
      (node (ref "U3") (pin "104") (pinfunction "CCLK_104") (pintype "bidirectional"))
    )
    (net (code "227") (name "Net-(U12-TDO)") (class "Default")
      (node (ref "R41") (pin "1") (pinfunction "1_1") (pintype "passive"))
      (node (ref "U12") (pin "17") (pinfunction "TDO_17") (pintype "output"))
    )
    (net (code "228") (name "Net-(U12-~{CE})") (class "Default")
      (node (ref "R35") (pin "1") (pinfunction "1_1") (pintype "passive"))
      (node (ref "R37") (pin "1") (pinfunction "1_1") (pintype "passive"))
      (node (ref "U12") (pin "10") (pinfunction "~{CE}_10") (pintype "input"))
      (node (ref "U3") (pin "103") (pinfunction "DONE_103") (pintype "bidirectional"))
    )
    (net (code "229") (name "Net-(U12-~{CF})") (class "Default")
      (node (ref "R36") (pin "1") (pinfunction "1_1") (pintype "passive"))
      (node (ref "S7") (pin "2") (pinfunction "2_2") (pintype "passive"))
      (node (ref "U12") (pin "7") (pinfunction "~{CF}_7") (pintype "open_collector"))
      (node (ref "U3") (pin "207") (pinfunction "PROG_B_207") (pintype "input"))
    )
    (net (code "230") (name "Net-(U14-C1+)") (class "Default")
      (node (ref "C44") (pin "1") (pinfunction "1_1") (pintype "passive"))
      (node (ref "U14") (pin "1") (pinfunction "C1+_1") (pintype "passive"))
    )
    (net (code "231") (name "Net-(U14-C1-)") (class "Default")
      (node (ref "C44") (pin "2") (pinfunction "2_2") (pintype "passive"))
      (node (ref "U14") (pin "3") (pinfunction "C1-_3") (pintype "passive"))
    )
    (net (code "232") (name "Net-(U14-C2+)") (class "Default")
      (node (ref "C52") (pin "1") (pinfunction "1_1") (pintype "passive"))
      (node (ref "U14") (pin "4") (pinfunction "C2+_4") (pintype "passive"))
    )
    (net (code "233") (name "Net-(U14-C2-)") (class "Default")
      (node (ref "C52") (pin "2") (pinfunction "2_2") (pintype "passive"))
      (node (ref "U14") (pin "5") (pinfunction "C2-_5") (pintype "passive"))
    )
    (net (code "234") (name "Net-(U14-R1IN)") (class "Default")
      (node (ref "J2") (pin "2") (pinfunction "2_2") (pintype "passive"))
      (node (ref "U14") (pin "13") (pinfunction "R1IN_13") (pintype "input"))
    )
    (net (code "235") (name "Net-(U14-T1OUT)") (class "Default")
      (node (ref "J2") (pin "3") (pinfunction "3_3") (pintype "passive"))
      (node (ref "U14") (pin "14") (pinfunction "T1OUT_14") (pintype "output"))
    )
    (net (code "236") (name "Net-(U14-V+)") (class "Default")
      (node (ref "C50") (pin "1") (pinfunction "1_1") (pintype "passive"))
      (node (ref "U14") (pin "2") (pinfunction "V+_2") (pintype "power_in"))
    )
    (net (code "237") (name "Net-(U14-V-)") (class "Default")
      (node (ref "C66") (pin "2") (pinfunction "2_2") (pintype "passive"))
      (node (ref "U14") (pin "6") (pinfunction "V-_6") (pintype "power_in"))
    )
    (net (code "238") (name "Net-(USB2-D+)") (class "Default")
      (node (ref "R31") (pin "1") (pinfunction "1_1") (pintype "passive"))
      (node (ref "USB2") (pin "3") (pinfunction "D+_3") (pintype "passive"))
    )
    (net (code "239") (name "Net-(USB2-D-)") (class "Default")
      (node (ref "R29") (pin "1") (pinfunction "1_1") (pintype "passive"))
      (node (ref "USB2") (pin "2") (pinfunction "D-_2") (pintype "passive"))
    )
    (net (code "240") (name "Net-(USB2-VCC)") (class "Default")
      (node (ref "F3") (pin "1") (pinfunction "1_1") (pintype "passive"))
      (node (ref "USB2") (pin "1") (pinfunction "VCC_1") (pintype "passive"))
    )
    (net (code "241") (name "unconnected-(J2-MH1-Pad10)") (class "Default")
      (node (ref "J2") (pin "10") (pinfunction "MH1_10") (pintype "passive+no_connect"))
    )
    (net (code "242") (name "unconnected-(J2-MH2-Pad11)") (class "Default")
      (node (ref "J2") (pin "11") (pinfunction "MH2_11") (pintype "passive+no_connect"))
    )
    (net (code "243") (name "unconnected-(J2-Pad1)") (class "Default")
      (node (ref "J2") (pin "1") (pinfunction "1_1") (pintype "passive+no_connect"))
    )
    (net (code "244") (name "unconnected-(J2-Pad4)") (class "Default")
      (node (ref "J2") (pin "4") (pinfunction "4_4") (pintype "passive+no_connect"))
    )
    (net (code "245") (name "unconnected-(J2-Pad6)") (class "Default")
      (node (ref "J2") (pin "6") (pinfunction "6_6") (pintype "passive+no_connect"))
    )
    (net (code "246") (name "unconnected-(J2-Pad7)") (class "Default")
      (node (ref "J2") (pin "7") (pinfunction "7_7") (pintype "passive+no_connect"))
    )
    (net (code "247") (name "unconnected-(J2-Pad8)") (class "Default")
      (node (ref "J2") (pin "8") (pinfunction "8_8") (pintype "passive+no_connect"))
    )
    (net (code "248") (name "unconnected-(J2-Pad9)") (class "Default")
      (node (ref "J2") (pin "9") (pinfunction "9_9") (pintype "passive+no_connect"))
    )
    (net (code "249") (name "unconnected-(LCD1-D0-Pad7)") (class "Default")
      (node (ref "LCD1") (pin "7") (pinfunction "D0_7") (pintype "passive+no_connect"))
    )
    (net (code "250") (name "unconnected-(LCD1-D1-Pad8)") (class "Default")
      (node (ref "LCD1") (pin "8") (pinfunction "D1_8") (pintype "passive+no_connect"))
    )
    (net (code "251") (name "unconnected-(LCD1-D2-Pad9)") (class "Default")
      (node (ref "LCD1") (pin "9") (pinfunction "D2_9") (pintype "passive+no_connect"))
    )
    (net (code "252") (name "unconnected-(LCD1-D3-Pad10)") (class "Default")
      (node (ref "LCD1") (pin "10") (pinfunction "D3_10") (pintype "passive+no_connect"))
    )
    (net (code "253") (name "unconnected-(P5-Pad6)") (class "Default")
      (node (ref "P5") (pin "6") (pinfunction "6_6") (pintype "passive+no_connect"))
    )
    (net (code "254") (name "unconnected-(P5-Pad7)") (class "Default")
      (node (ref "P5") (pin "7") (pinfunction "7_7") (pintype "passive+no_connect"))
    )
    (net (code "255") (name "unconnected-(P5-Pad8)") (class "Default")
      (node (ref "P5") (pin "8") (pinfunction "8_8") (pintype "passive+no_connect"))
    )
    (net (code "256") (name "unconnected-(U1-CBUS2-Pad13)") (class "Default")
      (node (ref "U1") (pin "13") (pinfunction "CBUS2_13") (pintype "passive+no_connect"))
    )
    (net (code "257") (name "unconnected-(U1-CBUS3-Pad14)") (class "Default")
      (node (ref "U1") (pin "14") (pinfunction "CBUS3_14") (pintype "passive+no_connect"))
    )
    (net (code "258") (name "unconnected-(U1-CBUS4-Pad12)") (class "Default")
      (node (ref "U1") (pin "12") (pinfunction "CBUS4_12") (pintype "passive+no_connect"))
    )
    (net (code "259") (name "unconnected-(U1-CTS#-Pad11)") (class "Default")
      (node (ref "U1") (pin "11") (pinfunction "CTS#_11") (pintype "passive+no_connect"))
    )
    (net (code "260") (name "unconnected-(U1-DCD#-Pad10)") (class "Default")
      (node (ref "U1") (pin "10") (pinfunction "DCD#_10") (pintype "passive+no_connect"))
    )
    (net (code "261") (name "unconnected-(U1-DSR#-Pad9)") (class "Default")
      (node (ref "U1") (pin "9") (pinfunction "DSR#_9") (pintype "passive+no_connect"))
    )
    (net (code "262") (name "unconnected-(U1-DTR#-Pad2)") (class "Default")
      (node (ref "U1") (pin "2") (pinfunction "DTR#_2") (pintype "passive+no_connect"))
    )
    (net (code "263") (name "unconnected-(U1-NC-Pad8)") (class "Default")
      (node (ref "U1") (pin "8") (pinfunction "NC_8") (pintype "passive+no_connect"))
    )
    (net (code "264") (name "unconnected-(U1-NC-Pad24)") (class "Default")
      (node (ref "U1") (pin "24") (pinfunction "NC_24") (pintype "passive+no_connect"))
    )
    (net (code "265") (name "unconnected-(U1-OCSI-Pad27)") (class "Default")
      (node (ref "U1") (pin "27") (pinfunction "OCSI_27") (pintype "passive+no_connect"))
    )
    (net (code "266") (name "unconnected-(U1-OCSO-Pad28)") (class "Default")
      (node (ref "U1") (pin "28") (pinfunction "OCSO_28") (pintype "passive+no_connect"))
    )
    (net (code "267") (name "unconnected-(U1-RESET#-Pad19)") (class "Default")
      (node (ref "U1") (pin "19") (pinfunction "RESET#_19") (pintype "passive+no_connect"))
    )
    (net (code "268") (name "unconnected-(U1-RI#-Pad6)") (class "Default")
      (node (ref "U1") (pin "6") (pinfunction "RI#_6") (pintype "passive+no_connect"))
    )
    (net (code "269") (name "unconnected-(U1-RTS#-Pad3)") (class "Default")
      (node (ref "U1") (pin "3") (pinfunction "RTS#_3") (pintype "passive+no_connect"))
    )
    (net (code "270") (name "unconnected-(U2-NC-Pad28)") (class "Default")
      (node (ref "U2") (pin "28") (pinfunction "NC_28") (pintype "passive+no_connect"))
    )
    (net (code "271") (name "unconnected-(U9-ACBUS0-Pad26)") (class "Default")
      (node (ref "U9") (pin "26") (pinfunction "ACBUS0_26") (pintype "bidirectional+no_connect"))
    )
    (net (code "272") (name "unconnected-(U9-ACBUS1-Pad27)") (class "Default")
      (node (ref "U9") (pin "27") (pinfunction "ACBUS1_27") (pintype "bidirectional+no_connect"))
    )
    (net (code "273") (name "unconnected-(U9-ACBUS2-Pad28)") (class "Default")
      (node (ref "U9") (pin "28") (pinfunction "ACBUS2_28") (pintype "bidirectional+no_connect"))
    )
    (net (code "274") (name "unconnected-(U9-ACBUS3-Pad29)") (class "Default")
      (node (ref "U9") (pin "29") (pinfunction "ACBUS3_29") (pintype "bidirectional+no_connect"))
    )
    (net (code "275") (name "unconnected-(U9-ACBUS4-Pad30)") (class "Default")
      (node (ref "U9") (pin "30") (pinfunction "ACBUS4_30") (pintype "bidirectional+no_connect"))
    )
    (net (code "276") (name "unconnected-(U9-ACBUS5-Pad32)") (class "Default")
      (node (ref "U9") (pin "32") (pinfunction "ACBUS5_32") (pintype "bidirectional+no_connect"))
    )
    (net (code "277") (name "unconnected-(U9-ACBUS6-Pad33)") (class "Default")
      (node (ref "U9") (pin "33") (pinfunction "ACBUS6_33") (pintype "bidirectional+no_connect"))
    )
    (net (code "278") (name "unconnected-(U9-ACBUS7-Pad34)") (class "Default")
      (node (ref "U9") (pin "34") (pinfunction "ACBUS7_34") (pintype "bidirectional+no_connect"))
    )
    (net (code "279") (name "unconnected-(U9-ADBUS4-Pad21)") (class "Default")
      (node (ref "U9") (pin "21") (pinfunction "ADBUS4_21") (pintype "bidirectional+no_connect"))
    )
    (net (code "280") (name "unconnected-(U9-ADBUS5-Pad22)") (class "Default")
      (node (ref "U9") (pin "22") (pinfunction "ADBUS5_22") (pintype "bidirectional+no_connect"))
    )
    (net (code "281") (name "unconnected-(U9-ADBUS6-Pad23)") (class "Default")
      (node (ref "U9") (pin "23") (pinfunction "ADBUS6_23") (pintype "bidirectional+no_connect"))
    )
    (net (code "282") (name "unconnected-(U9-ADBUS7-Pad24)") (class "Default")
      (node (ref "U9") (pin "24") (pinfunction "ADBUS7_24") (pintype "bidirectional+no_connect"))
    )
    (net (code "283") (name "unconnected-(U9-BCBUS0-Pad48)") (class "Default")
      (node (ref "U9") (pin "48") (pinfunction "BCBUS0_48") (pintype "bidirectional+no_connect"))
    )
    (net (code "284") (name "unconnected-(U9-BCBUS1-Pad52)") (class "Default")
      (node (ref "U9") (pin "52") (pinfunction "BCBUS1_52") (pintype "bidirectional+no_connect"))
    )
    (net (code "285") (name "unconnected-(U9-BCBUS2-Pad53)") (class "Default")
      (node (ref "U9") (pin "53") (pinfunction "BCBUS2_53") (pintype "bidirectional+no_connect"))
    )
    (net (code "286") (name "unconnected-(U9-BCBUS3-Pad54)") (class "Default")
      (node (ref "U9") (pin "54") (pinfunction "BCBUS3_54") (pintype "bidirectional+no_connect"))
    )
    (net (code "287") (name "unconnected-(U9-BCBUS4-Pad55)") (class "Default")
      (node (ref "U9") (pin "55") (pinfunction "BCBUS4_55") (pintype "bidirectional+no_connect"))
    )
    (net (code "288") (name "unconnected-(U9-BCBUS5-Pad57)") (class "Default")
      (node (ref "U9") (pin "57") (pinfunction "BCBUS5_57") (pintype "bidirectional+no_connect"))
    )
    (net (code "289") (name "unconnected-(U9-BCBUS6-Pad58)") (class "Default")
      (node (ref "U9") (pin "58") (pinfunction "BCBUS6_58") (pintype "bidirectional+no_connect"))
    )
    (net (code "290") (name "unconnected-(U9-BCBUS7-Pad59)") (class "Default")
      (node (ref "U9") (pin "59") (pinfunction "BCBUS7_59") (pintype "bidirectional+no_connect"))
    )
    (net (code "291") (name "unconnected-(U9-BDBUS2-Pad40)") (class "Default")
      (node (ref "U9") (pin "40") (pinfunction "BDBUS2_40") (pintype "bidirectional+no_connect"))
    )
    (net (code "292") (name "unconnected-(U9-BDBUS3-Pad41)") (class "Default")
      (node (ref "U9") (pin "41") (pinfunction "BDBUS3_41") (pintype "bidirectional+no_connect"))
    )
    (net (code "293") (name "unconnected-(U9-BDBUS4-Pad43)") (class "Default")
      (node (ref "U9") (pin "43") (pinfunction "BDBUS4_43") (pintype "bidirectional+no_connect"))
    )
    (net (code "294") (name "unconnected-(U9-BDBUS5-Pad44)") (class "Default")
      (node (ref "U9") (pin "44") (pinfunction "BDBUS5_44") (pintype "bidirectional+no_connect"))
    )
    (net (code "295") (name "unconnected-(U9-BDBUS6-Pad45)") (class "Default")
      (node (ref "U9") (pin "45") (pinfunction "BDBUS6_45") (pintype "bidirectional+no_connect"))
    )
    (net (code "296") (name "unconnected-(U9-BDBUS7-Pad46)") (class "Default")
      (node (ref "U9") (pin "46") (pinfunction "BDBUS7_46") (pintype "bidirectional+no_connect"))
    )
    (net (code "297") (name "unconnected-(U9-PWREN#-Pad60)") (class "Default")
      (node (ref "U9") (pin "60") (pinfunction "PWREN#_60") (pintype "output+no_connect"))
    )
    (net (code "298") (name "unconnected-(U9-SUSPEND#-Pad36)") (class "Default")
      (node (ref "U9") (pin "36") (pinfunction "SUSPEND#_36") (pintype "output+no_connect"))
    )
    (net (code "299") (name "unconnected-(U11-NC-Pad6)") (class "Default")
      (node (ref "U11") (pin "6") (pinfunction "NC_6") (pintype "passive+no_connect"))
    )
    (net (code "300") (name "unconnected-(U11-NC-Pad7)") (class "Default")
      (node (ref "U11") (pin "7") (pinfunction "NC_7") (pintype "passive+no_connect"))
    )
    (net (code "301") (name "unconnected-(U12-DNC-Pad2)") (class "Default")
      (node (ref "U12") (pin "2") (pinfunction "DNC_2") (pintype "passive+no_connect"))
    )
    (net (code "302") (name "unconnected-(U12-DNC-Pad9)") (class "Default")
      (node (ref "U12") (pin "9") (pinfunction "DNC_9") (pintype "passive+no_connect"))
    )
    (net (code "303") (name "unconnected-(U12-DNC-Pad12)") (class "Default")
      (node (ref "U12") (pin "12") (pinfunction "DNC_12") (pintype "passive+no_connect"))
    )
    (net (code "304") (name "unconnected-(U12-DNC-Pad14)") (class "Default")
      (node (ref "U12") (pin "14") (pinfunction "DNC_14") (pintype "passive+no_connect"))
    )
    (net (code "305") (name "unconnected-(U12-DNC-Pad15)") (class "Default")
      (node (ref "U12") (pin "15") (pinfunction "DNC_15") (pintype "passive+no_connect"))
    )
    (net (code "306") (name "unconnected-(U12-DNC-Pad16)") (class "Default")
      (node (ref "U12") (pin "16") (pinfunction "DNC_16") (pintype "passive+no_connect"))
    )
    (net (code "307") (name "unconnected-(U12-~{CEO}-Pad13)") (class "Default")
      (node (ref "U12") (pin "13") (pinfunction "~{CEO}_13") (pintype "output+no_connect"))
    )
    (net (code "308") (name "unconnected-(U14-R2IN-Pad8)") (class "Default")
      (node (ref "U14") (pin "8") (pinfunction "R2IN_8") (pintype "input+no_connect"))
    )
    (net (code "309") (name "unconnected-(U14-R2OUT-Pad9)") (class "Default")
      (node (ref "U14") (pin "9") (pinfunction "R2OUT_9") (pintype "output+no_connect"))
    )
    (net (code "310") (name "unconnected-(U14-T2IN-Pad10)") (class "Default")
      (node (ref "U14") (pin "10") (pinfunction "T2IN_10") (pintype "input+no_connect"))
    )
    (net (code "311") (name "unconnected-(U14-T2OUT-Pad7)") (class "Default")
      (node (ref "U14") (pin "7") (pinfunction "T2OUT_7") (pintype "output+no_connect"))
    )
    (net (code "312") (name "unconnected-(USB1-NC-Pad4)") (class "Default")
      (node (ref "USB1") (pin "4") (pinfunction "NC_4") (pintype "passive+no_connect"))
    )
    (net (code "313") (name "unconnected-(USB1-VCC-Pad1)") (class "Default")
      (node (ref "USB1") (pin "1") (pinfunction "VCC_1") (pintype "passive+no_connect"))
    )
    (net (code "314") (name "unconnected-(USB2-NC-Pad4)") (class "Default")
      (node (ref "USB2") (pin "4") (pinfunction "NC_4") (pintype "passive+no_connect"))
    )
    (net (code "315") (name "unconnected-(VGA1-MH1-Pad16)") (class "Default")
      (node (ref "VGA1") (pin "16") (pinfunction "MH1_16") (pintype "passive+no_connect"))
    )
    (net (code "316") (name "unconnected-(VGA1-MH2-Pad17)") (class "Default")
      (node (ref "VGA1") (pin "17") (pinfunction "MH2_17") (pintype "passive+no_connect"))
    )
    (net (code "317") (name "unconnected-(VGA1-Pad4)") (class "Default")
      (node (ref "VGA1") (pin "4") (pinfunction "4_4") (pintype "passive+no_connect"))
    )
    (net (code "318") (name "unconnected-(VGA1-Pad9)") (class "Default")
      (node (ref "VGA1") (pin "9") (pinfunction "9_9") (pintype "passive+no_connect"))
    )
    (net (code "319") (name "unconnected-(VGA1-Pad12)") (class "Default")
      (node (ref "VGA1") (pin "12") (pinfunction "12_12") (pintype "passive+no_connect"))
    )
    (net (code "320") (name "unconnected-(VGA1-Pad15)") (class "Default")
      (node (ref "VGA1") (pin "15") (pinfunction "15_15") (pintype "passive+no_connect"))
    )
  )
)
